# NICBP_v3.net
KiCad netlist of a schematic drawn in EAGLE
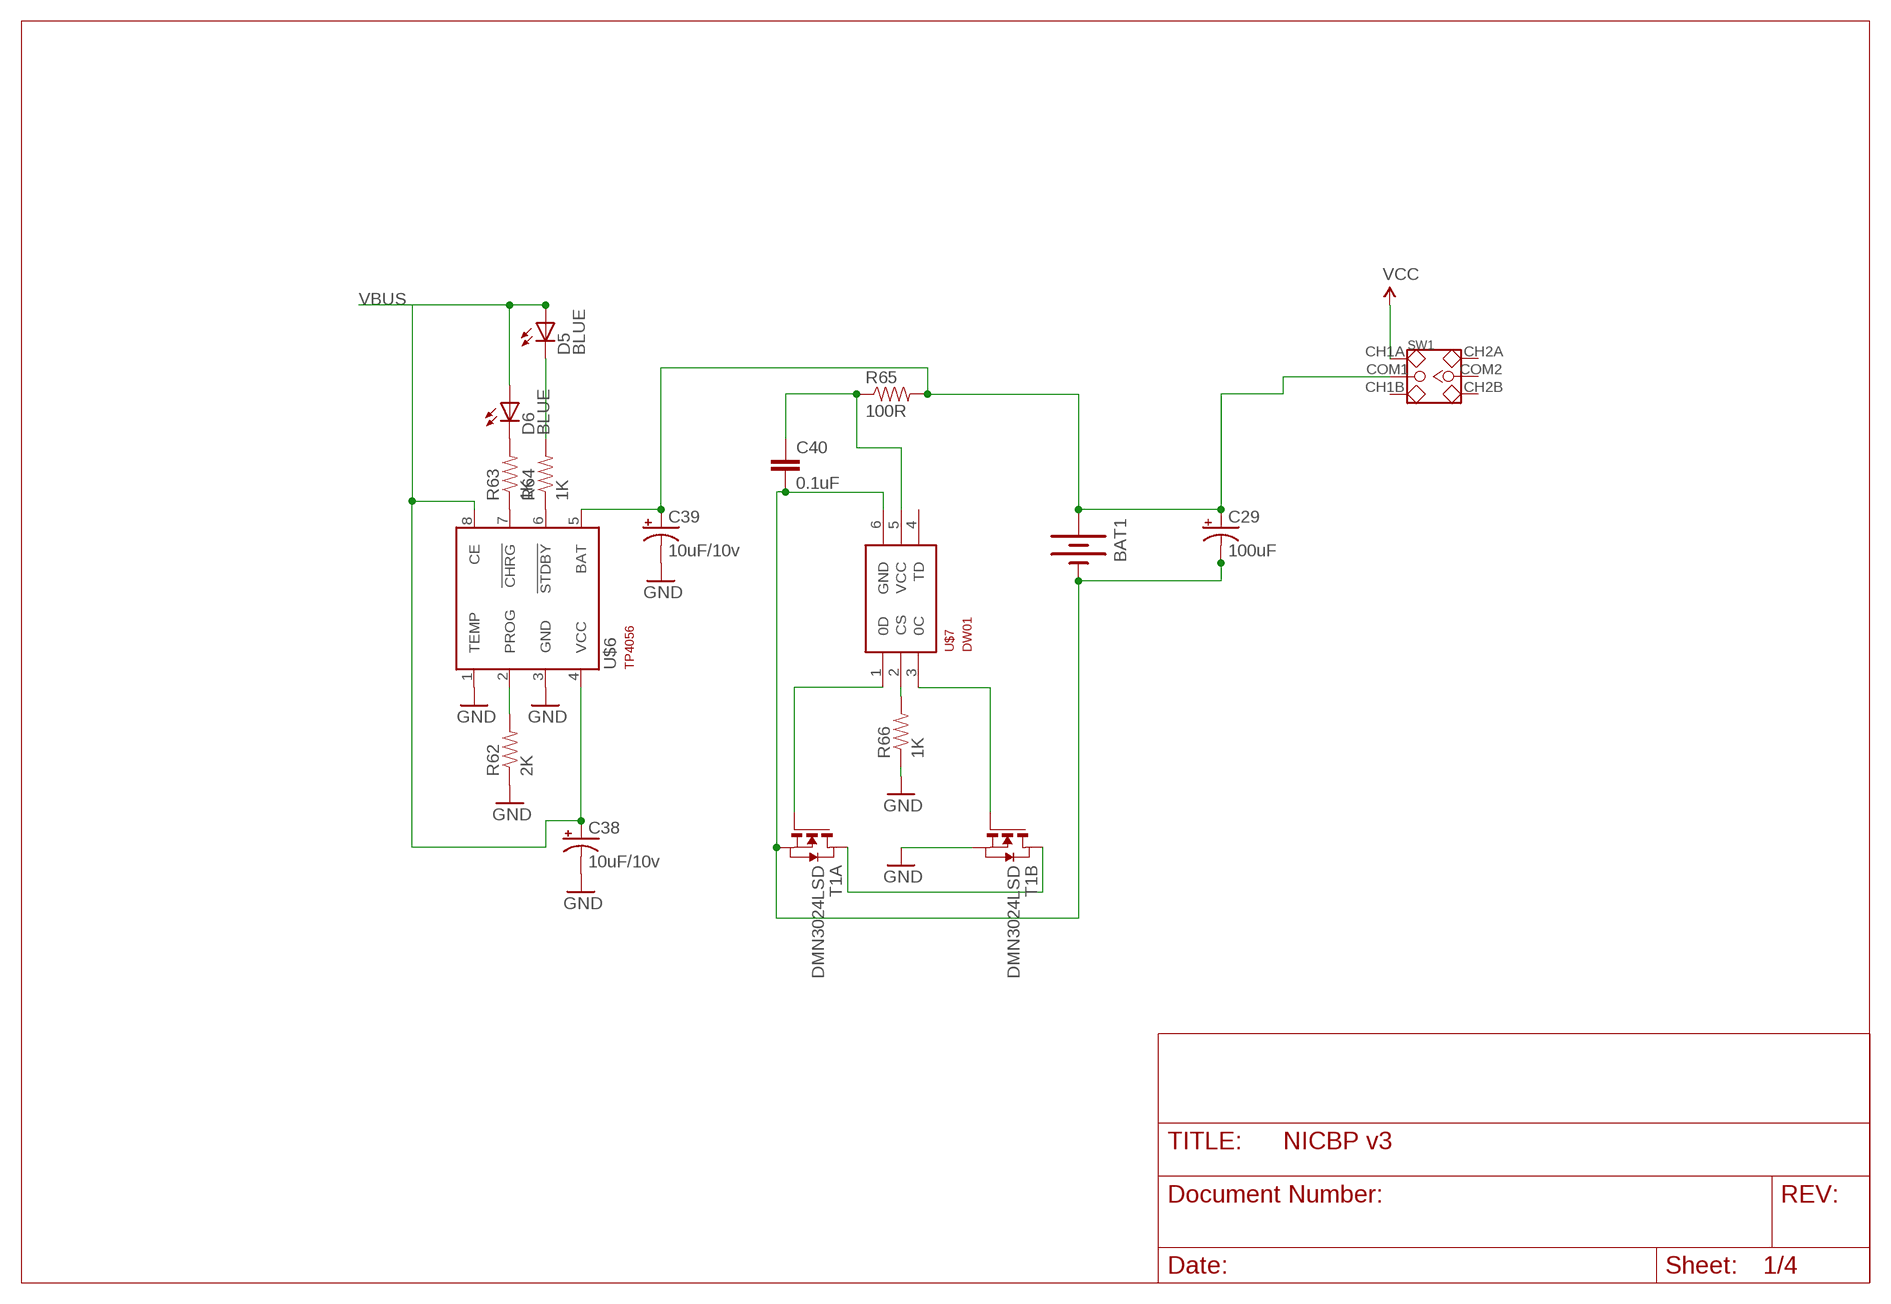
[diagram p0: schematic, sheet 1]
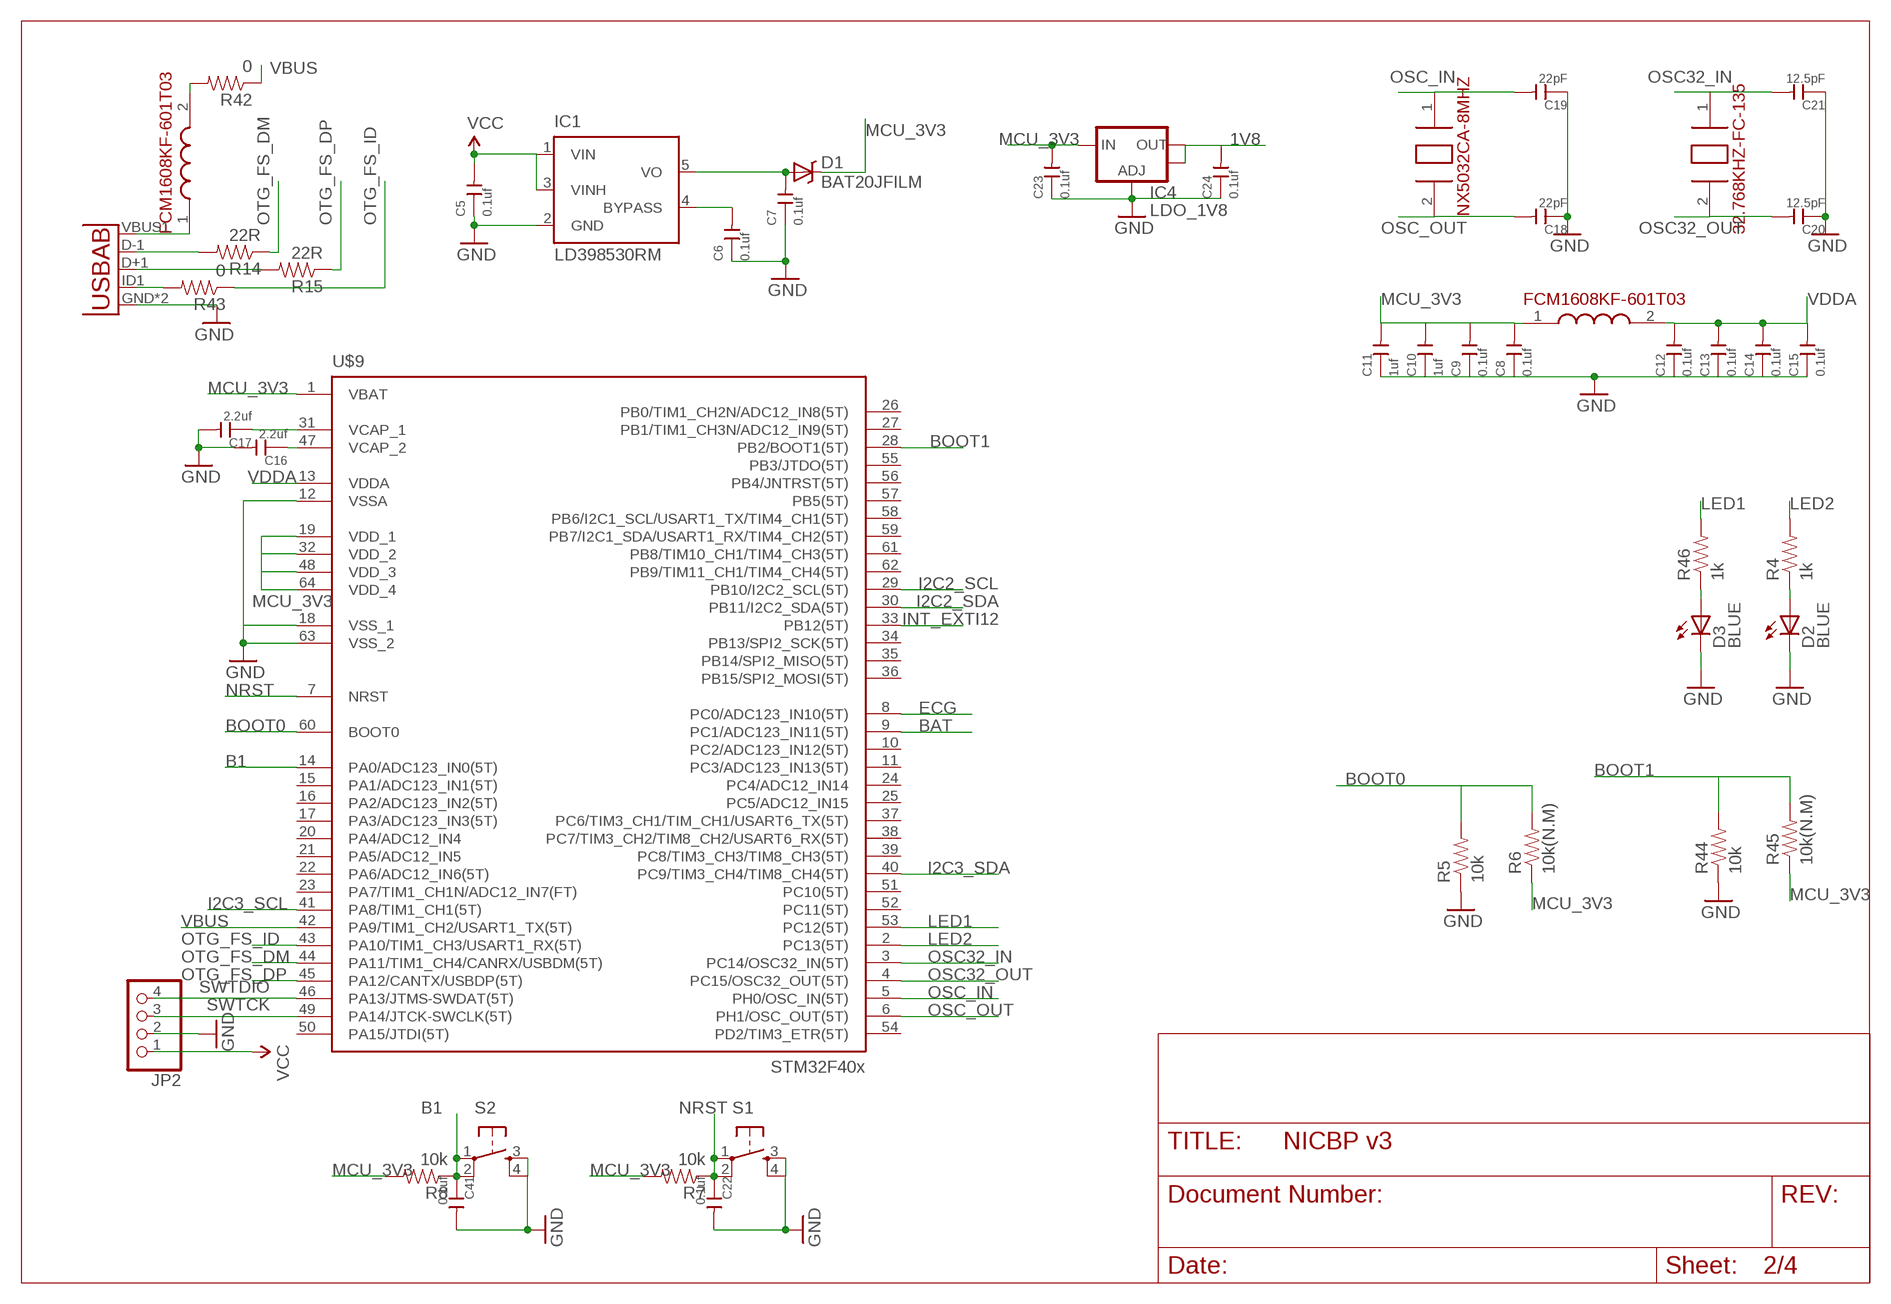
[diagram p1: schematic, sheet 2]
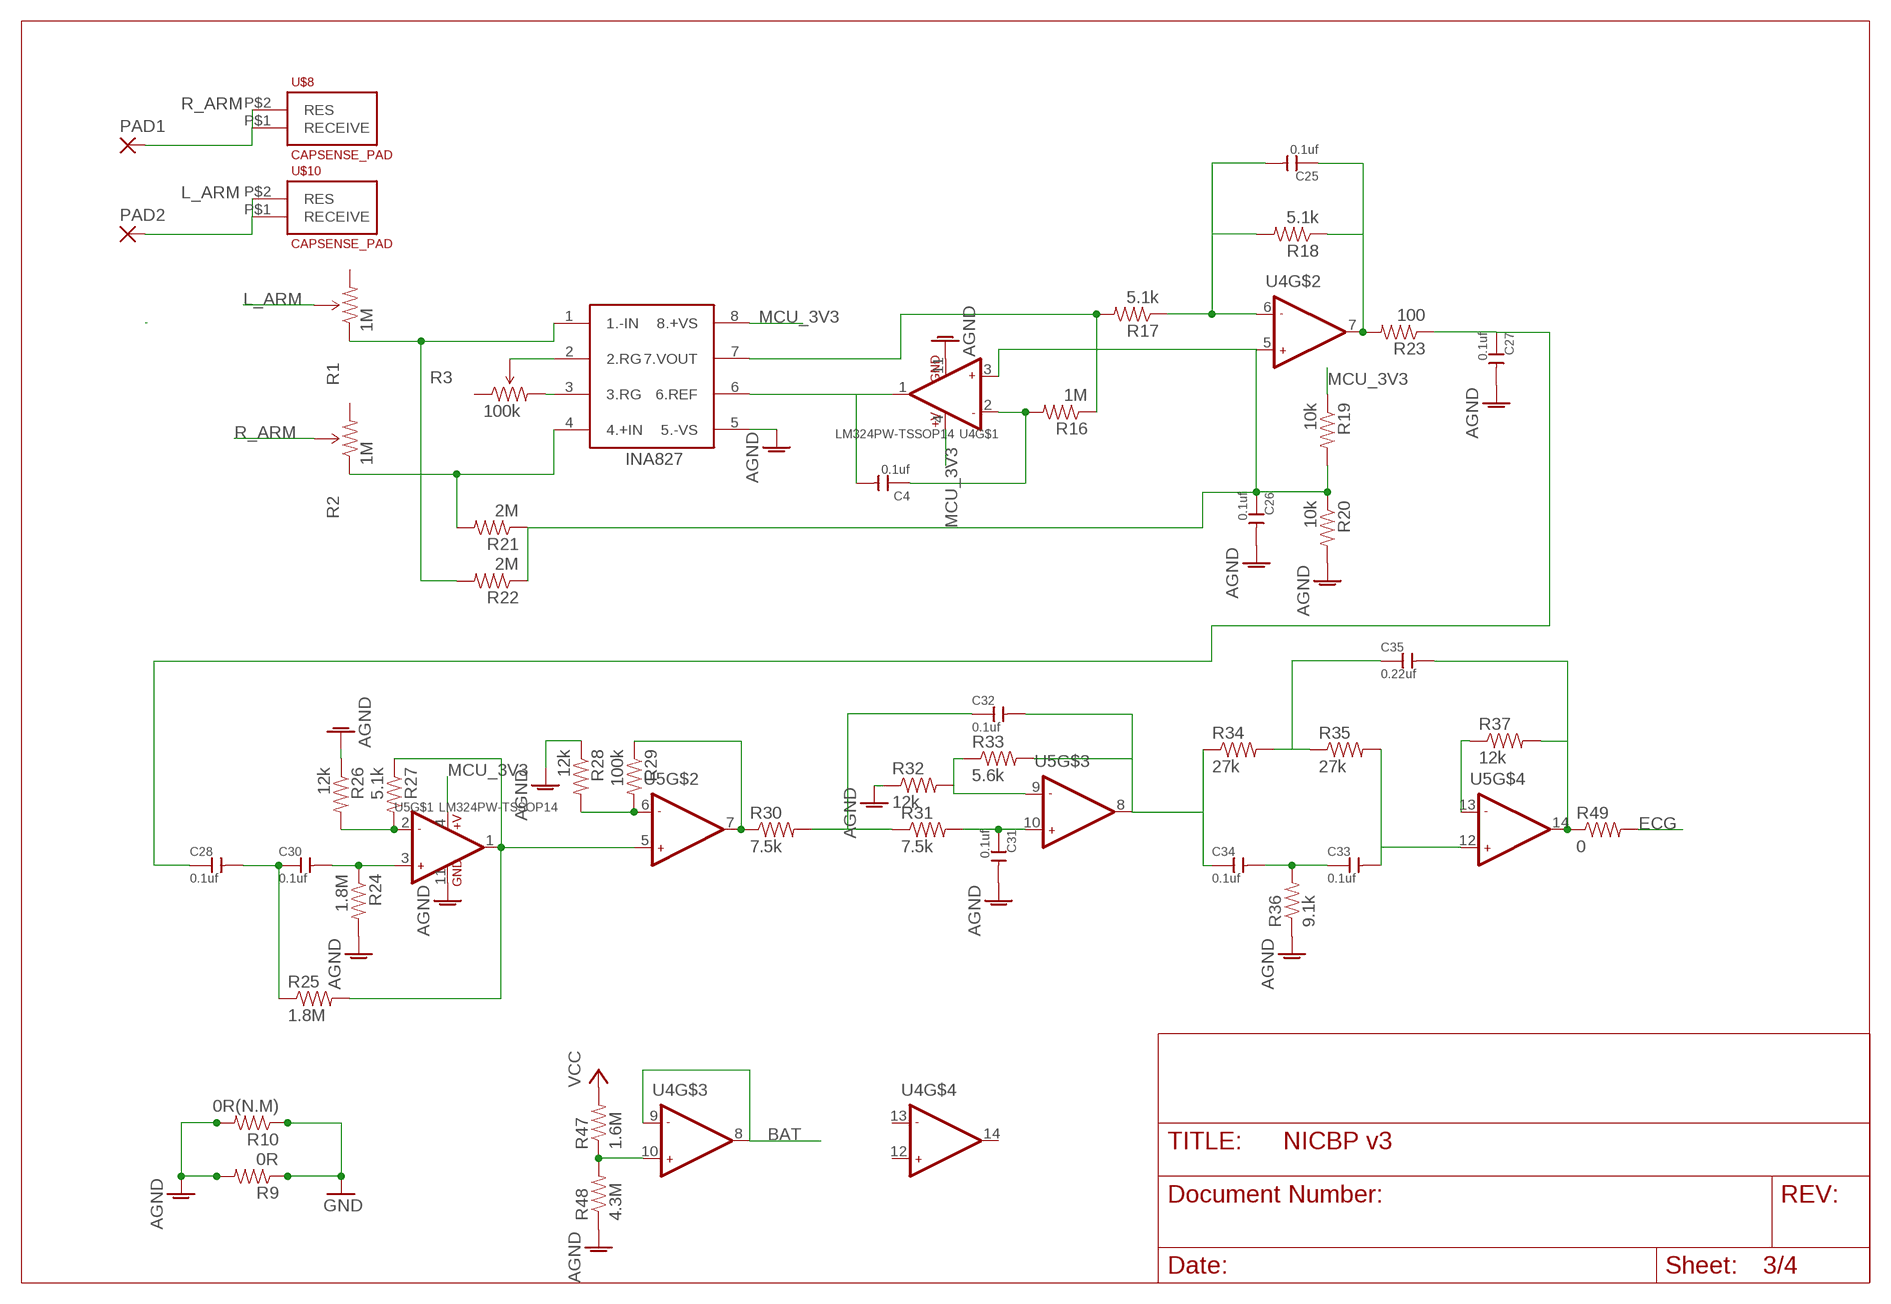
[diagram p2: schematic, sheet 3]
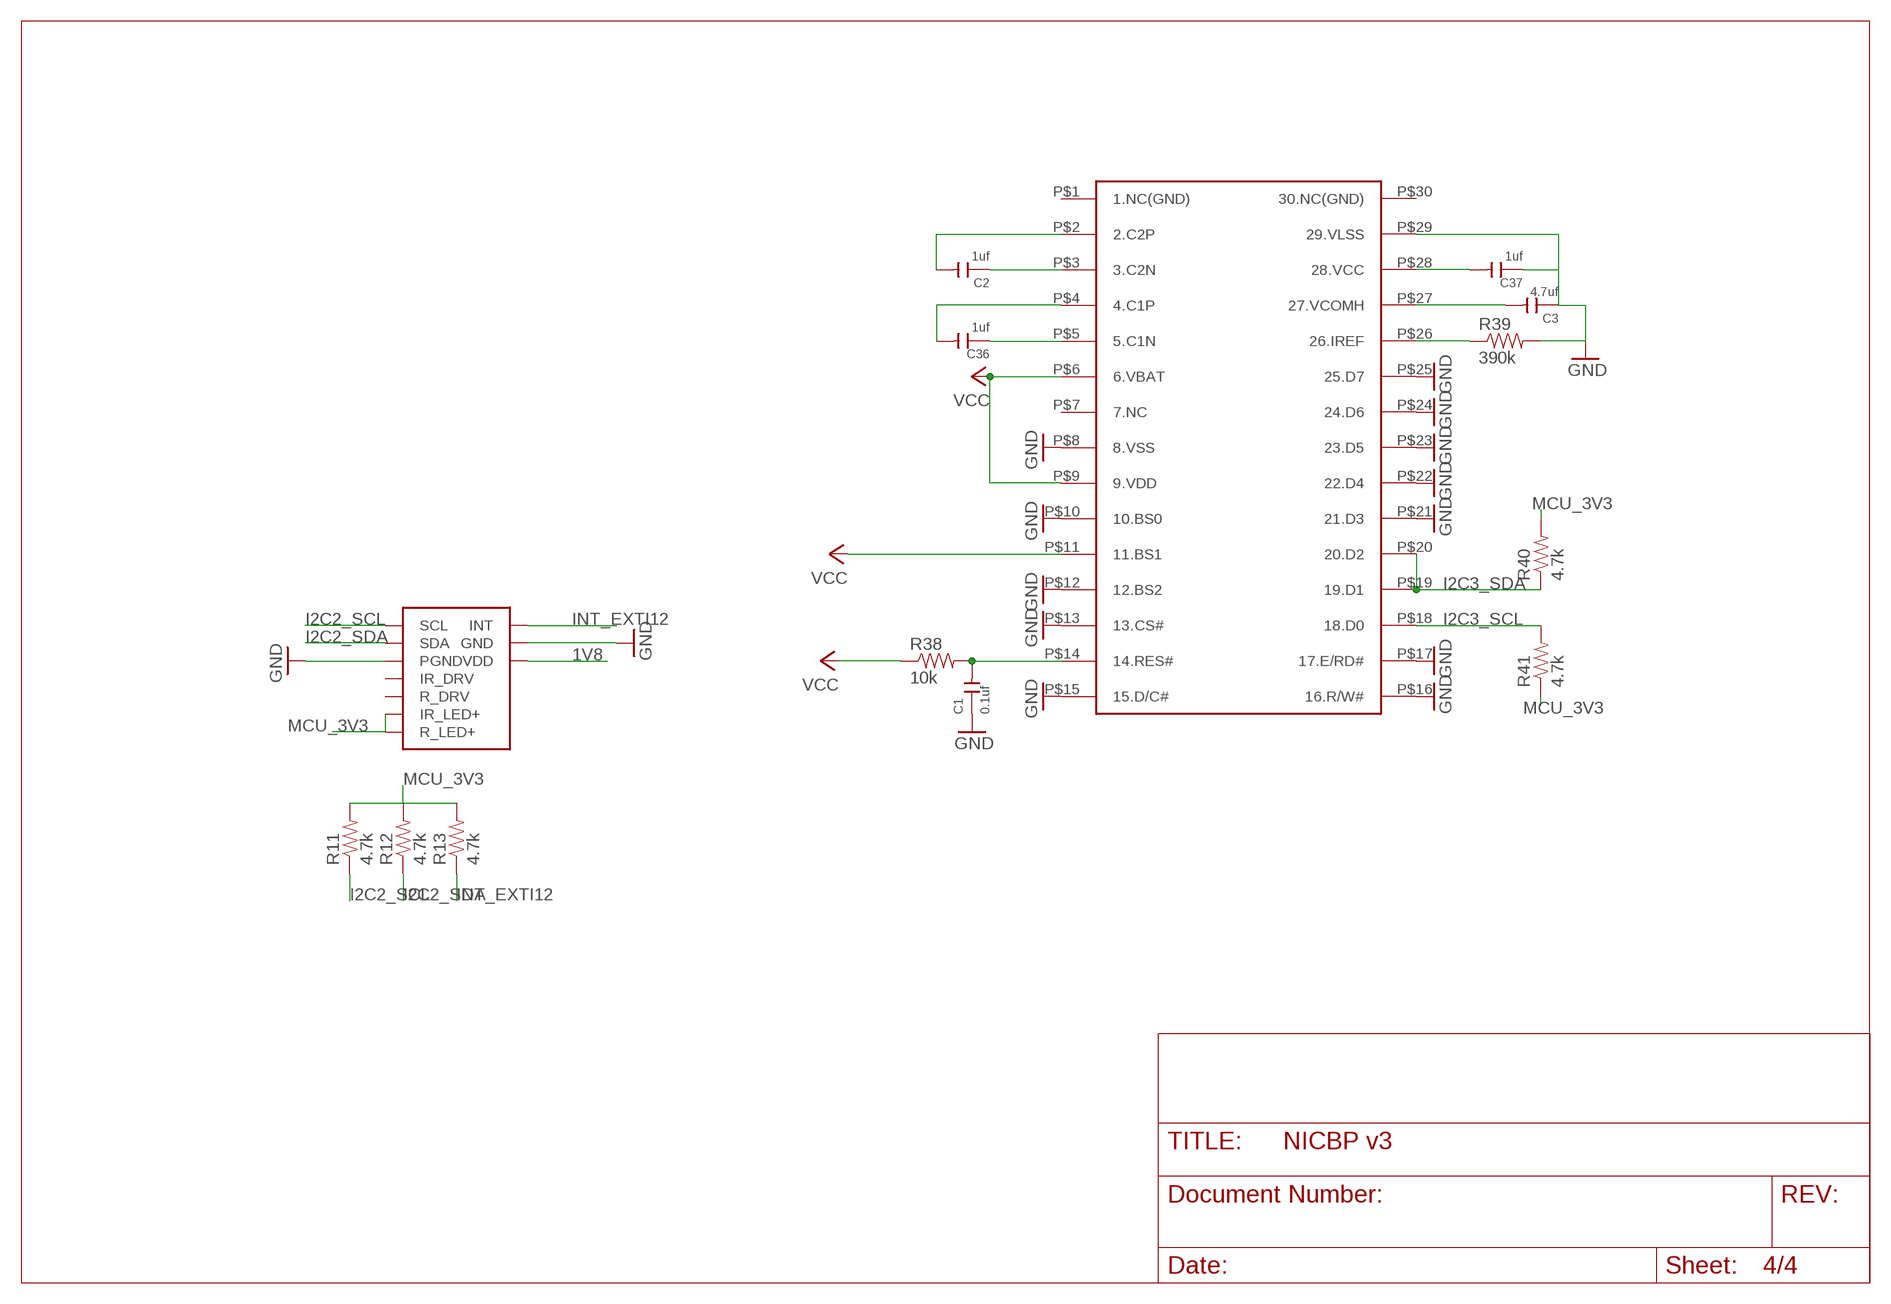
[diagram p3: schematic, sheet 4]

(export (version "E")
  (design (tool "Eeschema 10.0.6"))
  (components
    (comp (ref "BAT1")
      (value "BATTERYLIPO-TABS")
      (footprint "eagle-import:LIPO-110-TABS")
      (libsource (lib "eagle-import") (part "BATTERYLIPO-TABS"))
    )
    (comp (ref "C29")
      (value "100uF")
      (footprint "eagle-import:NIPPON_F80")
      (libsource (lib "eagle-import") (part "CAP_POLF80"))
    )
    (comp (ref "C38")
      (value "10uF/10v")
      (footprint "eagle-import:EIA3216-KIT")
      (libsource (lib "eagle-import") (part "CAP_POL1206-KIT"))
    )
    (comp (ref "C39")
      (value "10uF/10v")
      (footprint "eagle-import:EIA3216-KIT")
      (libsource (lib "eagle-import") (part "CAP_POL1206-KIT"))
    )
    (comp (ref "C40")
      (value "0.1uF")
      (footprint "eagle-import:0603-CAP")
      (libsource (lib "eagle-import") (part "0.1UF-100V-10%(0603)"))
    )
    (comp (ref "D5")
      (value "BLUE")
      (footprint "eagle-import:LED-0603")
      (libsource (lib "eagle-import") (part "LED-BLUE0603"))
    )
    (comp (ref "D6")
      (value "BLUE")
      (footprint "eagle-import:LED-0603")
      (libsource (lib "eagle-import") (part "LED-BLUE0603"))
    )
    (comp (ref "R62")
      (value "2K")
      (footprint "eagle-import:0603-RES")
      (libsource (lib "eagle-import") (part "1KOHM1/10W1%(0603)"))
    )
    (comp (ref "R63")
      (value "1K")
      (footprint "eagle-import:0603-RES")
      (libsource (lib "eagle-import") (part "1KOHM1/10W1%(0603)"))
    )
    (comp (ref "R64")
      (value "1K")
      (footprint "eagle-import:0603-RES")
      (libsource (lib "eagle-import") (part "1KOHM1/10W1%(0603)"))
    )
    (comp (ref "R65")
      (value "100R")
      (footprint "eagle-import:0603-RES")
      (libsource (lib "eagle-import") (part "1KOHM1/10W1%(0603)"))
    )
    (comp (ref "R66")
      (value "1K")
      (footprint "eagle-import:0603-RES")
      (libsource (lib "eagle-import") (part "1KOHM1/10W1%(0603)"))
    )
    (comp (ref "SW1")
      (value "SMD-TOGGLE-SWITCH-2CH(2X3P-7X3.5MM)")
      (footprint "eagle-import:SW6-2.54-SMD-7.0X3.5X1.5MM")
      (libsource (lib "eagle-import") (part "SMD-TOGGLE-SWITCH-2CH(2X3P-7X3.5MM)"))
    )
    (comp (ref "T1")
      (value "DMN3024LSD")
      (footprint "eagle-import:TSSOP-8")
      (libsource (lib "eagle-import") (part "DMN3024LSD"))
    )
    (comp (ref "U$6")
      (value "TP4056")
      (footprint "eagle-import:SOT23-8")
      (libsource (lib "eagle-import") (part "TP4056"))
    )
    (comp (ref "U$7")
      (value "DW01")
      (footprint "eagle-import:SOT23-6")
      (libsource (lib "eagle-import") (part "DW01"))
    )
    (comp (ref "C4")
      (value "0.1uf")
      (footprint "eagle-import:C0603")
      (fields (field (name "MPN") "CC0603KRX5R6BB475"))
      (libsource (lib "eagle-import") (part "CERAMIC-4.7UF-10V-10%-X5R(0603)"))
    )
    (comp (ref "C25")
      (value "0.1uf")
      (footprint "eagle-import:C0603")
      (fields (field (name "MPN") "CC0603KRX5R6BB475"))
      (libsource (lib "eagle-import") (part "CERAMIC-4.7UF-10V-10%-X5R(0603)"))
    )
    (comp (ref "C26")
      (value "0.1uf")
      (footprint "eagle-import:C0603")
      (fields (field (name "MPN") "CC0603KRX5R6BB475"))
      (libsource (lib "eagle-import") (part "CERAMIC-4.7UF-10V-10%-X5R(0603)"))
    )
    (comp (ref "C27")
      (value "0.1uf")
      (footprint "eagle-import:C0603")
      (fields (field (name "MPN") "CC0603KRX5R6BB475"))
      (libsource (lib "eagle-import") (part "CERAMIC-4.7UF-10V-10%-X5R(0603)"))
    )
    (comp (ref "C28")
      (value "0.1uf")
      (footprint "eagle-import:C0603")
      (fields (field (name "MPN") "CC0603KRX5R6BB475"))
      (libsource (lib "eagle-import") (part "CERAMIC-4.7UF-10V-10%-X5R(0603)"))
    )
    (comp (ref "C30")
      (value "0.1uf")
      (footprint "eagle-import:C0603")
      (fields (field (name "MPN") "CC0603KRX5R6BB475"))
      (libsource (lib "eagle-import") (part "CERAMIC-4.7UF-10V-10%-X5R(0603)"))
    )
    (comp (ref "C31")
      (value "0.1uf")
      (footprint "eagle-import:C0603")
      (fields (field (name "MPN") "CC0603KRX5R6BB475"))
      (libsource (lib "eagle-import") (part "CERAMIC-4.7UF-10V-10%-X5R(0603)"))
    )
    (comp (ref "C32")
      (value "0.1uf")
      (footprint "eagle-import:C0603")
      (fields (field (name "MPN") "CC0603KRX5R6BB475"))
      (libsource (lib "eagle-import") (part "CERAMIC-4.7UF-10V-10%-X5R(0603)"))
    )
    (comp (ref "C33")
      (value "0.1uf")
      (footprint "eagle-import:C0603")
      (fields (field (name "MPN") "CC0603KRX5R6BB475"))
      (libsource (lib "eagle-import") (part "CERAMIC-4.7UF-10V-10%-X5R(0603)"))
    )
    (comp (ref "C34")
      (value "0.1uf")
      (footprint "eagle-import:C0603")
      (fields (field (name "MPN") "CC0603KRX5R6BB475"))
      (libsource (lib "eagle-import") (part "CERAMIC-4.7UF-10V-10%-X5R(0603)"))
    )
    (comp (ref "C35")
      (value "0.22uf")
      (footprint "eagle-import:C0603")
      (fields (field (name "MPN") "CC0603KRX5R6BB475"))
      (libsource (lib "eagle-import") (part "CERAMIC-4.7UF-10V-10%-X5R(0603)"))
    )
    (comp (ref "PAD1")
      (value "3,17/1,3")
      (footprint "eagle-import:3,17_1,3")
      (libsource (lib "eagle-import") (part "3,17/1,3"))
    )
    (comp (ref "PAD2")
      (value "3,17/1,3")
      (footprint "eagle-import:3,17_1,3")
      (libsource (lib "eagle-import") (part "3,17/1,3"))
    )
    (comp (ref "R1")
      (value "1M")
      (footprint "eagle-import:TRIMPOT_TC33")
      (libsource (lib "eagle-import") (part "TRIMPOT-2"))
    )
    (comp (ref "R2")
      (value "1M")
      (footprint "eagle-import:TRIMPOT_TC33")
      (libsource (lib "eagle-import") (part "TRIMPOT-2"))
    )
    (comp (ref "R3")
      (value "100k")
      (footprint "eagle-import:TRIMPOT_TC33")
      (libsource (lib "eagle-import") (part "TRIMPOT-2"))
    )
    (comp (ref "R9")
      (value "0R")
      (footprint "eagle-import:0603")
      (libsource (lib "eagle-import") (part "0OHM1/10W5%(0603)"))
    )
    (comp (ref "R10")
      (value "0R(N.M)")
      (footprint "eagle-import:0603")
      (libsource (lib "eagle-import") (part "0OHM1/10W5%(0603)"))
    )
    (comp (ref "R16")
      (value "1M")
      (footprint "eagle-import:0603")
      (libsource (lib "eagle-import") (part "0OHM1/10W5%(0603)"))
    )
    (comp (ref "R17")
      (value "5.1k")
      (footprint "eagle-import:0603")
      (libsource (lib "eagle-import") (part "0OHM1/10W5%(0603)"))
    )
    (comp (ref "R18")
      (value "5.1k")
      (footprint "eagle-import:0603")
      (libsource (lib "eagle-import") (part "0OHM1/10W5%(0603)"))
    )
    (comp (ref "R19")
      (value "10k")
      (footprint "eagle-import:0603")
      (libsource (lib "eagle-import") (part "0OHM1/10W5%(0603)"))
    )
    (comp (ref "R20")
      (value "10k")
      (footprint "eagle-import:0603")
      (libsource (lib "eagle-import") (part "0OHM1/10W5%(0603)"))
    )
    (comp (ref "R21")
      (value "2M")
      (footprint "eagle-import:0603")
      (libsource (lib "eagle-import") (part "0OHM1/10W5%(0603)"))
    )
    (comp (ref "R22")
      (value "2M")
      (footprint "eagle-import:0603")
      (libsource (lib "eagle-import") (part "0OHM1/10W5%(0603)"))
    )
    (comp (ref "R23")
      (value "100")
      (footprint "eagle-import:0603")
      (libsource (lib "eagle-import") (part "0OHM1/10W5%(0603)"))
    )
    (comp (ref "R24")
      (value "1.8M")
      (footprint "eagle-import:0603")
      (libsource (lib "eagle-import") (part "0OHM1/10W5%(0603)"))
    )
    (comp (ref "R25")
      (value "1.8M")
      (footprint "eagle-import:0603")
      (libsource (lib "eagle-import") (part "0OHM1/10W5%(0603)"))
    )
    (comp (ref "R26")
      (value "12k")
      (footprint "eagle-import:0603")
      (libsource (lib "eagle-import") (part "0OHM1/10W5%(0603)"))
    )
    (comp (ref "R27")
      (value "5.1k")
      (footprint "eagle-import:0603")
      (libsource (lib "eagle-import") (part "0OHM1/10W5%(0603)"))
    )
    (comp (ref "R28")
      (value "12k")
      (footprint "eagle-import:0603")
      (libsource (lib "eagle-import") (part "0OHM1/10W5%(0603)"))
    )
    (comp (ref "R29")
      (value "100k")
      (footprint "eagle-import:0603")
      (libsource (lib "eagle-import") (part "0OHM1/10W5%(0603)"))
    )
    (comp (ref "R30")
      (value "7.5k")
      (footprint "eagle-import:0603")
      (libsource (lib "eagle-import") (part "0OHM1/10W5%(0603)"))
    )
    (comp (ref "R31")
      (value "7.5k")
      (footprint "eagle-import:0603")
      (libsource (lib "eagle-import") (part "0OHM1/10W5%(0603)"))
    )
    (comp (ref "R32")
      (value "12k")
      (footprint "eagle-import:0603")
      (libsource (lib "eagle-import") (part "0OHM1/10W5%(0603)"))
    )
    (comp (ref "R33")
      (value "5.6k")
      (footprint "eagle-import:0603")
      (libsource (lib "eagle-import") (part "0OHM1/10W5%(0603)"))
    )
    (comp (ref "R34")
      (value "27k")
      (footprint "eagle-import:0603")
      (libsource (lib "eagle-import") (part "0OHM1/10W5%(0603)"))
    )
    (comp (ref "R35")
      (value "27k")
      (footprint "eagle-import:0603")
      (libsource (lib "eagle-import") (part "0OHM1/10W5%(0603)"))
    )
    (comp (ref "R36")
      (value "9.1k")
      (footprint "eagle-import:0603")
      (libsource (lib "eagle-import") (part "0OHM1/10W5%(0603)"))
    )
    (comp (ref "R37")
      (value "12k")
      (footprint "eagle-import:0603")
      (libsource (lib "eagle-import") (part "0OHM1/10W5%(0603)"))
    )
    (comp (ref "R47")
      (value "1.6M")
      (footprint "eagle-import:0603")
      (libsource (lib "eagle-import") (part "0OHM1/10W5%(0603)"))
    )
    (comp (ref "R48")
      (value "4.3M")
      (footprint "eagle-import:0603")
      (libsource (lib "eagle-import") (part "0OHM1/10W5%(0603)"))
    )
    (comp (ref "R49")
      (value "0")
      (footprint "eagle-import:0603")
      (libsource (lib "eagle-import") (part "0OHM1/10W5%(0603)"))
    )
    (comp (ref "U$5")
      (value "INA827")
      (footprint "eagle-import:INA827")
      (libsource (lib "eagle-import") (part "INA827"))
    )
    (comp (ref "U$8")
      (value "CAPSENSE_PAD")
      (footprint "eagle-import:CAPSENSE_PAD")
      (libsource (lib "eagle-import") (part "CAPSENSE_PAD"))
    )
    (comp (ref "U$10")
      (value "CAPSENSE_PAD")
      (footprint "eagle-import:CAPSENSE_PAD")
      (libsource (lib "eagle-import") (part "CAPSENSE_PAD"))
    )
    (comp (ref "U4")
      (value "LM324PW-TSSOP14")
      (footprint "eagle-import:TSSOP14-0.65-5X4.4MM")
      (fields (field (name "MPN") "LM324PW"))
      (libsource (lib "eagle-import") (part "AMPLIFIER-LM324PW(TSSOP14)"))
    )
    (comp (ref "U5")
      (value "LM324PW-TSSOP14")
      (footprint "eagle-import:TSSOP14-0.65-5X4.4MM")
      (fields (field (name "MPN") "LM324PW"))
      (libsource (lib "eagle-import") (part "AMPLIFIER-LM324PW(TSSOP14)"))
    )
    (comp (ref "C5")
      (value "0.1uf")
      (footprint "eagle-import:C0603")
      (fields (field (name "MPN") "CC0603KRX5R6BB475"))
      (libsource (lib "eagle-import") (part "CERAMIC-4.7UF-10V-10%-X5R(0603)"))
    )
    (comp (ref "C6")
      (value "0.1uf")
      (footprint "eagle-import:C0603")
      (fields (field (name "MPN") "CC0603KRX5R6BB475"))
      (libsource (lib "eagle-import") (part "CERAMIC-4.7UF-10V-10%-X5R(0603)"))
    )
    (comp (ref "C7")
      (value "0.1uf")
      (footprint "eagle-import:C0603")
      (fields (field (name "MPN") "CC0603KRX5R6BB475"))
      (libsource (lib "eagle-import") (part "CERAMIC-4.7UF-10V-10%-X5R(0603)"))
    )
    (comp (ref "C8")
      (value "0.1uf")
      (footprint "eagle-import:C0603")
      (fields (field (name "MPN") "CC0603KRX5R6BB475"))
      (libsource (lib "eagle-import") (part "CERAMIC-4.7UF-10V-10%-X5R(0603)"))
    )
    (comp (ref "C9")
      (value "0.1uf")
      (footprint "eagle-import:C0603")
      (fields (field (name "MPN") "CC0603KRX5R6BB475"))
      (libsource (lib "eagle-import") (part "CERAMIC-4.7UF-10V-10%-X5R(0603)"))
    )
    (comp (ref "C10")
      (value "1uf")
      (footprint "eagle-import:C0603")
      (fields (field (name "MPN") "CC0603KRX5R6BB475"))
      (libsource (lib "eagle-import") (part "CERAMIC-4.7UF-10V-10%-X5R(0603)"))
    )
    (comp (ref "C11")
      (value "1uf")
      (footprint "eagle-import:C0603")
      (fields (field (name "MPN") "CC0603KRX5R6BB475"))
      (libsource (lib "eagle-import") (part "CERAMIC-4.7UF-10V-10%-X5R(0603)"))
    )
    (comp (ref "C12")
      (value "0.1uf")
      (footprint "eagle-import:C0603")
      (fields (field (name "MPN") "CC0603KRX5R6BB475"))
      (libsource (lib "eagle-import") (part "CERAMIC-4.7UF-10V-10%-X5R(0603)"))
    )
    (comp (ref "C13")
      (value "0.1uf")
      (footprint "eagle-import:C0603")
      (fields (field (name "MPN") "CC0603KRX5R6BB475"))
      (libsource (lib "eagle-import") (part "CERAMIC-4.7UF-10V-10%-X5R(0603)"))
    )
    (comp (ref "C14")
      (value "0.1uf")
      (footprint "eagle-import:C0603")
      (fields (field (name "MPN") "CC0603KRX5R6BB475"))
      (libsource (lib "eagle-import") (part "CERAMIC-4.7UF-10V-10%-X5R(0603)"))
    )
    (comp (ref "C15")
      (value "0.1uf")
      (footprint "eagle-import:C0603")
      (fields (field (name "MPN") "CC0603KRX5R6BB475"))
      (libsource (lib "eagle-import") (part "CERAMIC-4.7UF-10V-10%-X5R(0603)"))
    )
    (comp (ref "C16")
      (value "2.2uf")
      (footprint "eagle-import:C0603")
      (fields (field (name "MPN") "CC0603KRX5R6BB475"))
      (libsource (lib "eagle-import") (part "CERAMIC-4.7UF-10V-10%-X5R(0603)"))
    )
    (comp (ref "C17")
      (value "2.2uf")
      (footprint "eagle-import:C0603")
      (fields (field (name "MPN") "CC0603KRX5R6BB475"))
      (libsource (lib "eagle-import") (part "CERAMIC-4.7UF-10V-10%-X5R(0603)"))
    )
    (comp (ref "C18")
      (value "22pF")
      (footprint "eagle-import:C0603")
      (fields (field (name "MPN") "CC0603KRX5R6BB475"))
      (libsource (lib "eagle-import") (part "CERAMIC-4.7UF-10V-10%-X5R(0603)"))
    )
    (comp (ref "C19")
      (value "22pF")
      (footprint "eagle-import:C0603")
      (fields (field (name "MPN") "CC0603KRX5R6BB475"))
      (libsource (lib "eagle-import") (part "CERAMIC-4.7UF-10V-10%-X5R(0603)"))
    )
    (comp (ref "C20")
      (value "12.5pF")
      (footprint "eagle-import:C0603")
      (fields (field (name "MPN") "CC0603KRX5R6BB475"))
      (libsource (lib "eagle-import") (part "CERAMIC-4.7UF-10V-10%-X5R(0603)"))
    )
    (comp (ref "C21")
      (value "12.5pF")
      (footprint "eagle-import:C0603")
      (fields (field (name "MPN") "CC0603KRX5R6BB475"))
      (libsource (lib "eagle-import") (part "CERAMIC-4.7UF-10V-10%-X5R(0603)"))
    )
    (comp (ref "C22")
      (value "0.1uf")
      (footprint "eagle-import:C0603")
      (fields (field (name "MPN") "CC0603KRX5R6BB475"))
      (libsource (lib "eagle-import") (part "CERAMIC-4.7UF-10V-10%-X5R(0603)"))
    )
    (comp (ref "C23")
      (value "0.1uf")
      (footprint "eagle-import:C0603")
      (fields (field (name "MPN") "CC0603KRX5R6BB475"))
      (libsource (lib "eagle-import") (part "CERAMIC-4.7UF-10V-10%-X5R(0603)"))
    )
    (comp (ref "C24")
      (value "0.1uf")
      (footprint "eagle-import:C0603")
      (fields (field (name "MPN") "CC0603KRX5R6BB475"))
      (libsource (lib "eagle-import") (part "CERAMIC-4.7UF-10V-10%-X5R(0603)"))
    )
    (comp (ref "C41")
      (value "0.1uf")
      (footprint "eagle-import:C0603")
      (fields (field (name "MPN") "CC0603KRX5R6BB475"))
      (libsource (lib "eagle-import") (part "CERAMIC-4.7UF-10V-10%-X5R(0603)"))
    )
    (comp (ref "D1")
      (value "BAT20JFILM")
      (footprint "eagle-import:SOD-323")
      (libsource (lib "eagle-import") (part "BAT20JFILM"))
    )
    (comp (ref "D2")
      (value "BLUE")
      (footprint "eagle-import:LED-0603")
      (libsource (lib "eagle-import") (part "LED-BLUE0603"))
    )
    (comp (ref "D3")
      (value "BLUE")
      (footprint "eagle-import:LED-0603")
      (libsource (lib "eagle-import") (part "LED-BLUE0603"))
    )
    (comp (ref "IC1")
      (value "LD398530RM")
      (footprint "eagle-import:SOT23-5L")
      (libsource (lib "eagle-import") (part "LD3985M30R"))
    )
    (comp (ref "IC4")
      (value "LDO_1V8")
      (footprint "eagle-import:SOT223")
      (libsource (lib "eagle-import") (part "V_REG_LM1117SOT223"))
    )
    (comp (ref "JP2")
      (value "PINHD-1X4")
      (footprint "eagle-import:1X04")
      (libsource (lib "eagle-import") (part "PINHD-1X4"))
    )
    (comp (ref "R4")
      (value "1k")
      (footprint "eagle-import:0603")
      (libsource (lib "eagle-import") (part "0OHM1/10W5%(0603)"))
    )
    (comp (ref "R5")
      (value "10k")
      (footprint "eagle-import:0603")
      (libsource (lib "eagle-import") (part "0OHM1/10W5%(0603)"))
    )
    (comp (ref "R6")
      (value "10k(N.M)")
      (footprint "eagle-import:0603")
      (libsource (lib "eagle-import") (part "0OHM1/10W5%(0603)"))
    )
    (comp (ref "R7")
      (value "10k")
      (footprint "eagle-import:0603")
      (libsource (lib "eagle-import") (part "0OHM1/10W5%(0603)"))
    )
    (comp (ref "R8")
      (value "10k")
      (footprint "eagle-import:0603")
      (libsource (lib "eagle-import") (part "0OHM1/10W5%(0603)"))
    )
    (comp (ref "R14")
      (value "22R")
      (footprint "eagle-import:0603-RES")
      (libsource (lib "eagle-import") (part "390OHM1/10W1%(0603)"))
    )
    (comp (ref "R15")
      (value "22R")
      (footprint "eagle-import:0603-RES")
      (libsource (lib "eagle-import") (part "390OHM1/10W1%(0603)"))
    )
    (comp (ref "R42")
      (value "0")
      (footprint "eagle-import:0603-RES")
      (libsource (lib "eagle-import") (part "390OHM1/10W1%(0603)"))
    )
    (comp (ref "R43")
      (value "0")
      (footprint "eagle-import:0603-RES")
      (libsource (lib "eagle-import") (part "390OHM1/10W1%(0603)"))
    )
    (comp (ref "R44")
      (value "10k")
      (footprint "eagle-import:0603")
      (libsource (lib "eagle-import") (part "0OHM1/10W5%(0603)"))
    )
    (comp (ref "R45")
      (value "10k(N.M)")
      (footprint "eagle-import:0603")
      (libsource (lib "eagle-import") (part "0OHM1/10W5%(0603)"))
    )
    (comp (ref "R46")
      (value "1k")
      (footprint "eagle-import:0603")
      (libsource (lib "eagle-import") (part "0OHM1/10W5%(0603)"))
    )
    (comp (ref "S1")
      (value "TAC_SWITCHSMD")
      (footprint "eagle-import:TACTILE_SWITCH_SMD")
      (libsource (lib "eagle-import") (part "TAC_SWITCHSMD"))
    )
    (comp (ref "S2")
      (value "TAC_SWITCHSMD")
      (footprint "eagle-import:TACTILE_SWITCH_SMD")
      (libsource (lib "eagle-import") (part "TAC_SWITCHSMD"))
    )
    (comp (ref "U$2")
      (value "NX5032CA-8MHZ")
      (footprint "eagle-import:NX5032CA-8MHZ")
      (libsource (lib "eagle-import") (part "NX5032CA-8MHZ"))
    )
    (comp (ref "U$3")
      (value "FCM1608KF-601T03")
      (footprint "eagle-import:FCM1608KF-601T03")
      (libsource (lib "eagle-import") (part "FCM1608KF-601T03"))
    )
    (comp (ref "U$4")
      (value "32.768KHZ-FC-135")
      (footprint "eagle-import:32.768KHZ-FC-135")
      (libsource (lib "eagle-import") (part "32.768KHZ-FC-135"))
    )
    (comp (ref "U$9")
      (value "STM32F405R")
      (footprint "eagle-import:TQFP64")
      (libsource (lib "eagle-import") (part "STM32F405R"))
    )
    (comp (ref "U$15")
      (value "FCM1608KF-601T03")
      (footprint "eagle-import:FCM1608KF-601T03")
      (libsource (lib "eagle-import") (part "FCM1608KF-601T03"))
    )
    (comp (ref "U1")
      (value "USB\"\"")
      (footprint "eagle-import:USB-MICRO-SMD")
      (libsource (lib "eagle-import") (part "USB{dblquote}{dblquote}"))
    )
    (comp (ref "C1")
      (value "0.1uf")
      (footprint "eagle-import:C0603")
      (fields (field (name "MPN") "CC0603KRX5R6BB475"))
      (libsource (lib "eagle-import") (part "CERAMIC-4.7UF-10V-10%-X5R(0603)"))
    )
    (comp (ref "C2")
      (value "1uf")
      (footprint "eagle-import:C0603")
      (fields (field (name "MPN") "CC0603KRX5R6BB475"))
      (libsource (lib "eagle-import") (part "CERAMIC-4.7UF-10V-10%-X5R(0603)"))
    )
    (comp (ref "C3")
      (value "4.7uf")
      (footprint "eagle-import:C0603")
      (fields (field (name "MPN") "CC0603KRX5R6BB475"))
      (libsource (lib "eagle-import") (part "CERAMIC-4.7UF-10V-10%-X5R(0603)"))
    )
    (comp (ref "C36")
      (value "1uf")
      (footprint "eagle-import:C0603")
      (fields (field (name "MPN") "CC0603KRX5R6BB475"))
      (libsource (lib "eagle-import") (part "CERAMIC-4.7UF-10V-10%-X5R(0603)"))
    )
    (comp (ref "C37")
      (value "1uf")
      (footprint "eagle-import:C0603")
      (fields (field (name "MPN") "CC0603KRX5R6BB475"))
      (libsource (lib "eagle-import") (part "CERAMIC-4.7UF-10V-10%-X5R(0603)"))
    )
    (comp (ref "R11")
      (value "4.7k")
      (footprint "eagle-import:0603")
      (libsource (lib "eagle-import") (part "0OHM1/10W5%(0603)"))
    )
    (comp (ref "R12")
      (value "4.7k")
      (footprint "eagle-import:0603")
      (libsource (lib "eagle-import") (part "0OHM1/10W5%(0603)"))
    )
    (comp (ref "R13")
      (value "4.7k")
      (footprint "eagle-import:0603")
      (libsource (lib "eagle-import") (part "0OHM1/10W5%(0603)"))
    )
    (comp (ref "R38")
      (value "10k")
      (footprint "eagle-import:0603")
      (libsource (lib "eagle-import") (part "0OHM1/10W5%(0603)"))
    )
    (comp (ref "R39")
      (value "390k")
      (footprint "eagle-import:0603")
      (libsource (lib "eagle-import") (part "0OHM1/10W5%(0603)"))
    )
    (comp (ref "R40")
      (value "4.7k")
      (footprint "eagle-import:0603")
      (libsource (lib "eagle-import") (part "0OHM1/10W5%(0603)"))
    )
    (comp (ref "R41")
      (value "4.7k")
      (footprint "eagle-import:0603")
      (libsource (lib "eagle-import") (part "0OHM1/10W5%(0603)"))
    )
    (comp (ref "U$12")
      (value "MAX30100")
      (footprint "eagle-import:MAX30100")
      (libsource (lib "eagle-import") (part "MAX30100"))
    )
    (comp (ref "U$13")
      (value "ER-OLED0.96")
      (footprint "eagle-import:ER-OLED0.96")
      (libsource (lib "eagle-import") (part "ER-OLED0.96"))
    )
  )
  (nets
    (net (code "1") (name "1V8") (class "Default")
      (node (ref "C24") (pin "2") (pinfunction "2_2") (pintype "passive"))
      (node (ref "IC4") (pin "2") (pinfunction "OUT_2") (pintype "output"))
      (node (ref "IC4") (pin "4") (pinfunction "OUT_4") (pintype "output"))
      (node (ref "U$12") (pin "11") (pinfunction "VDD_11") (pintype "bidirectional"))
    )
    (net (code "2") (name "AGND") (class "Default")
      (node (ref "C26") (pin "2") (pinfunction "2_2") (pintype "passive"))
      (node (ref "C27") (pin "2") (pinfunction "2_2") (pintype "passive"))
      (node (ref "C31") (pin "2") (pinfunction "2_2") (pintype "passive"))
      (node (ref "R10") (pin "2") (pinfunction "2_2") (pintype "passive"))
      (node (ref "R20") (pin "2") (pinfunction "2_2") (pintype "passive"))
      (node (ref "R24") (pin "2") (pinfunction "2_2") (pintype "passive"))
      (node (ref "R26") (pin "1") (pinfunction "1_1") (pintype "passive"))
      (node (ref "R28") (pin "1") (pinfunction "1_1") (pintype "passive"))
      (node (ref "R32") (pin "1") (pinfunction "1_1") (pintype "passive"))
      (node (ref "R36") (pin "1") (pinfunction "1_1") (pintype "passive"))
      (node (ref "R48") (pin "1") (pinfunction "1_1") (pintype "passive"))
      (node (ref "R9") (pin "2") (pinfunction "2_2") (pintype "passive"))
      (node (ref "U$5") (pin "5") (pinfunction "5.-VS_5") (pintype "bidirectional"))
      (node (ref "U4") (pin "11") (pinfunction "GND_11") (pintype "power_in"))
      (node (ref "U5") (pin "11") (pinfunction "GND_11") (pintype "power_in"))
    )
    (net (code "3") (name "B1") (class "Default")
      (node (ref "C41") (pin "1") (pinfunction "1_1") (pintype "passive"))
      (node (ref "R8") (pin "1") (pinfunction "1_1") (pintype "passive"))
      (node (ref "S2") (pin "1") (pinfunction "1_1") (pintype "passive"))
      (node (ref "S2") (pin "2") (pinfunction "2_2") (pintype "passive"))
      (node (ref "U$9") (pin "14") (pinfunction "PA0/ADC123_IN0(5T)_14") (pintype "bidirectional"))
    )
    (net (code "4") (name "BAT") (class "Default")
      (node (ref "U$9") (pin "9") (pinfunction "PC1/ADC123_IN11(5T)_9") (pintype "bidirectional"))
      (node (ref "U4") (pin "8") (pinfunction "OUT2_8") (pintype "output"))
      (node (ref "U4") (pin "9") (pinfunction "-IN2_9") (pintype "input"))
    )
    (net (code "5") (name "BOOT0") (class "Default")
      (node (ref "R5") (pin "2") (pinfunction "2_2") (pintype "passive"))
      (node (ref "R6") (pin "2") (pinfunction "2_2") (pintype "passive"))
      (node (ref "U$9") (pin "60") (pinfunction "BOOT0_60") (pintype "bidirectional"))
    )
    (net (code "6") (name "BOOT1") (class "Default")
      (node (ref "R44") (pin "2") (pinfunction "2_2") (pintype "passive"))
      (node (ref "R45") (pin "2") (pinfunction "2_2") (pintype "passive"))
      (node (ref "U$9") (pin "28") (pinfunction "PB2/BOOT1(5T)_28") (pintype "bidirectional"))
    )
    (net (code "7") (name "ECG") (class "Default")
      (node (ref "R49") (pin "2") (pinfunction "2_2") (pintype "passive"))
      (node (ref "U$9") (pin "8") (pinfunction "PC0/ADC123_IN10(5T)_8") (pintype "bidirectional"))
    )
    (net (code "8") (name "GND") (class "Default")
      (node (ref "C1") (pin "1") (pinfunction "1_1") (pintype "passive"))
      (node (ref "C10") (pin "1") (pinfunction "1_1") (pintype "passive"))
      (node (ref "C11") (pin "1") (pinfunction "1_1") (pintype "passive"))
      (node (ref "C12") (pin "1") (pinfunction "1_1") (pintype "passive"))
      (node (ref "C13") (pin "1") (pinfunction "1_1") (pintype "passive"))
      (node (ref "C14") (pin "1") (pinfunction "1_1") (pintype "passive"))
      (node (ref "C15") (pin "1") (pinfunction "1_1") (pintype "passive"))
      (node (ref "C16") (pin "2") (pinfunction "2_2") (pintype "passive"))
      (node (ref "C17") (pin "2") (pinfunction "2_2") (pintype "passive"))
      (node (ref "C18") (pin "1") (pinfunction "1_1") (pintype "passive"))
      (node (ref "C19") (pin "1") (pinfunction "1_1") (pintype "passive"))
      (node (ref "C20") (pin "1") (pinfunction "1_1") (pintype "passive"))
      (node (ref "C21") (pin "1") (pinfunction "1_1") (pintype "passive"))
      (node (ref "C22") (pin "2") (pinfunction "2_2") (pintype "passive"))
      (node (ref "C23") (pin "1") (pinfunction "1_1") (pintype "passive"))
      (node (ref "C24") (pin "1") (pinfunction "1_1") (pintype "passive"))
      (node (ref "C3") (pin "1") (pinfunction "1_1") (pintype "passive"))
      (node (ref "C37") (pin "1") (pinfunction "1_1") (pintype "passive"))
      (node (ref "C38") (pin "C") (pinfunction "-_C") (pintype "passive"))
      (node (ref "C39") (pin "C") (pinfunction "-_C") (pintype "passive"))
      (node (ref "C41") (pin "2") (pinfunction "2_2") (pintype "passive"))
      (node (ref "C5") (pin "1") (pinfunction "1_1") (pintype "passive"))
      (node (ref "C6") (pin "1") (pinfunction "1_1") (pintype "passive"))
      (node (ref "C7") (pin "1") (pinfunction "1_1") (pintype "passive"))
      (node (ref "C8") (pin "1") (pinfunction "1_1") (pintype "passive"))
      (node (ref "C9") (pin "1") (pinfunction "1_1") (pintype "passive"))
      (node (ref "D2") (pin "C") (pinfunction "C_C") (pintype "passive"))
      (node (ref "D3") (pin "C") (pinfunction "C_C") (pintype "passive"))
      (node (ref "IC1") (pin "2") (pinfunction "GND_2") (pintype "power_in"))
      (node (ref "IC4") (pin "1") (pinfunction "ADJ_1") (pintype "input"))
      (node (ref "JP2") (pin "2") (pinfunction "2_2") (pintype "passive"))
      (node (ref "R10") (pin "1") (pinfunction "1_1") (pintype "passive"))
      (node (ref "R39") (pin "2") (pinfunction "2_2") (pintype "passive"))
      (node (ref "R44") (pin "1") (pinfunction "1_1") (pintype "passive"))
      (node (ref "R5") (pin "1") (pinfunction "1_1") (pintype "passive"))
      (node (ref "R62") (pin "1") (pinfunction "1_1") (pintype "passive"))
      (node (ref "R66") (pin "1") (pinfunction "1_1") (pintype "passive"))
      (node (ref "R9") (pin "1") (pinfunction "1_1") (pintype "passive"))
      (node (ref "S1") (pin "3") (pinfunction "3_3") (pintype "passive"))
      (node (ref "S1") (pin "4") (pinfunction "4_4") (pintype "passive"))
      (node (ref "S2") (pin "3") (pinfunction "3_3") (pintype "passive"))
      (node (ref "S2") (pin "4") (pinfunction "4_4") (pintype "passive"))
      (node (ref "T1") (pin "6") (pinfunction "S_6") (pintype "passive"))
      (node (ref "T1") (pin "7") (pinfunction "S_7") (pintype "passive"))
      (node (ref "U$12") (pin "12") (pinfunction "GND_12") (pintype "bidirectional"))
      (node (ref "U$12") (pin "4") (pinfunction "PGND_4") (pintype "bidirectional"))
      (node (ref "U$13") (pin "P$10") (pinfunction "10.BS0_P$10") (pintype "bidirectional"))
      (node (ref "U$13") (pin "P$12") (pinfunction "12.BS2_P$12") (pintype "bidirectional"))
      (node (ref "U$13") (pin "P$13") (pinfunction "13.CS#_P$13") (pintype "bidirectional"))
      (node (ref "U$13") (pin "P$15") (pinfunction "15.D/C#_P$15") (pintype "bidirectional"))
      (node (ref "U$13") (pin "P$16") (pinfunction "16.R/W#_P$16") (pintype "bidirectional"))
      (node (ref "U$13") (pin "P$17") (pinfunction "17.E/RD#_P$17") (pintype "bidirectional"))
      (node (ref "U$13") (pin "P$21") (pinfunction "21.D3_P$21") (pintype "bidirectional"))
      (node (ref "U$13") (pin "P$22") (pinfunction "22.D4_P$22") (pintype "bidirectional"))
      (node (ref "U$13") (pin "P$23") (pinfunction "23.D5_P$23") (pintype "bidirectional"))
      (node (ref "U$13") (pin "P$24") (pinfunction "24.D6_P$24") (pintype "bidirectional"))
      (node (ref "U$13") (pin "P$25") (pinfunction "25.D7_P$25") (pintype "bidirectional"))
      (node (ref "U$13") (pin "P$29") (pinfunction "29.VLSS_P$29") (pintype "bidirectional"))
      (node (ref "U$13") (pin "P$8") (pinfunction "8.VSS_P$8") (pintype "bidirectional"))
      (node (ref "U$6") (pin "1") (pinfunction "TEMP_1") (pintype "bidirectional"))
      (node (ref "U$6") (pin "3") (pinfunction "GND_3") (pintype "bidirectional"))
      (node (ref "U$9") (pin "12") (pinfunction "VSSA_12") (pintype "bidirectional"))
      (node (ref "U$9") (pin "18") (pinfunction "VSS_1_18") (pintype "bidirectional"))
      (node (ref "U$9") (pin "63") (pinfunction "VSS_2_63") (pintype "bidirectional"))
      (node (ref "U1") (pin "GND") (pinfunction "GND_GND") (pintype "bidirectional"))
      (node (ref "U1") (pin "GND1") (pinfunction "GND_GND1") (pintype "bidirectional"))
    )
    (net (code "9") (name "I2C2_SCL") (class "Default")
      (node (ref "R11") (pin "1") (pinfunction "1_1") (pintype "passive"))
      (node (ref "U$12") (pin "2") (pinfunction "SCL_2") (pintype "bidirectional"))
      (node (ref "U$9") (pin "29") (pinfunction "PB10/I2C2_SCL(5T)_29") (pintype "bidirectional"))
    )
    (net (code "10") (name "I2C2_SDA") (class "Default")
      (node (ref "R12") (pin "1") (pinfunction "1_1") (pintype "passive"))
      (node (ref "U$12") (pin "3") (pinfunction "SDA_3") (pintype "bidirectional"))
      (node (ref "U$9") (pin "30") (pinfunction "PB11/I2C2_SDA(5T)_30") (pintype "bidirectional"))
    )
    (net (code "11") (name "I2C3_SCL") (class "Default")
      (node (ref "R41") (pin "2") (pinfunction "2_2") (pintype "passive"))
      (node (ref "U$13") (pin "P$18") (pinfunction "18.D0_P$18") (pintype "bidirectional"))
      (node (ref "U$9") (pin "41") (pinfunction "PA8/TIM1_CH1(5T)_41") (pintype "bidirectional"))
    )
    (net (code "12") (name "I2C3_SDA") (class "Default")
      (node (ref "R40") (pin "1") (pinfunction "1_1") (pintype "passive"))
      (node (ref "U$13") (pin "P$19") (pinfunction "19.D1_P$19") (pintype "bidirectional"))
      (node (ref "U$13") (pin "P$20") (pinfunction "20.D2_P$20") (pintype "bidirectional"))
      (node (ref "U$9") (pin "40") (pinfunction "PC9/TIM3_CH4/TIM8_CH4(5T)_40") (pintype "bidirectional"))
    )
    (net (code "13") (name "INT_EXTI12") (class "Default")
      (node (ref "R13") (pin "1") (pinfunction "1_1") (pintype "passive"))
      (node (ref "U$12") (pin "13") (pinfunction "INT_13") (pintype "bidirectional"))
      (node (ref "U$9") (pin "33") (pinfunction "PB12(5T)_33") (pintype "bidirectional"))
    )
    (net (code "14") (name "LED1") (class "Default")
      (node (ref "R46") (pin "2") (pinfunction "2_2") (pintype "passive"))
      (node (ref "U$9") (pin "53") (pinfunction "PC12(5T)_53") (pintype "bidirectional"))
    )
    (net (code "15") (name "LED2") (class "Default")
      (node (ref "R4") (pin "2") (pinfunction "2_2") (pintype "passive"))
      (node (ref "U$9") (pin "2") (pinfunction "PC13(5T)_2") (pintype "bidirectional"))
    )
    (net (code "16") (name "L_ARM") (class "Default")
      (node (ref "PAD2") (pin "1") (pinfunction "P_1") (pintype "passive"))
      (node (ref "R1") (pin "2") (pinfunction "WIPER_2") (pintype "passive"))
      (node (ref "U$10") (pin "P$1") (pinfunction "RECEIVE_P$1") (pintype "bidirectional"))
      (node (ref "U$10") (pin "P$2") (pinfunction "RES_P$2") (pintype "bidirectional"))
    )
    (net (code "17") (name "MCU_3V3") (class "Default")
      (node (ref "C10") (pin "2") (pinfunction "2_2") (pintype "passive"))
      (node (ref "C11") (pin "2") (pinfunction "2_2") (pintype "passive"))
      (node (ref "C23") (pin "2") (pinfunction "2_2") (pintype "passive"))
      (node (ref "C8") (pin "2") (pinfunction "2_2") (pintype "passive"))
      (node (ref "C9") (pin "2") (pinfunction "2_2") (pintype "passive"))
      (node (ref "D1") (pin "1") (pinfunction "C_1") (pintype "passive"))
      (node (ref "IC4") (pin "3") (pinfunction "IN_3") (pintype "input"))
      (node (ref "R11") (pin "2") (pinfunction "2_2") (pintype "passive"))
      (node (ref "R12") (pin "2") (pinfunction "2_2") (pintype "passive"))
      (node (ref "R13") (pin "2") (pinfunction "2_2") (pintype "passive"))
      (node (ref "R19") (pin "1") (pinfunction "1_1") (pintype "passive"))
      (node (ref "R40") (pin "2") (pinfunction "2_2") (pintype "passive"))
      (node (ref "R41") (pin "1") (pinfunction "1_1") (pintype "passive"))
      (node (ref "R45") (pin "1") (pinfunction "1_1") (pintype "passive"))
      (node (ref "R6") (pin "1") (pinfunction "1_1") (pintype "passive"))
      (node (ref "R7") (pin "2") (pinfunction "2_2") (pintype "passive"))
      (node (ref "R8") (pin "2") (pinfunction "2_2") (pintype "passive"))
      (node (ref "U$12") (pin "10") (pinfunction "IR_LED+_10") (pintype "bidirectional"))
      (node (ref "U$12") (pin "9") (pinfunction "R_LED+_9") (pintype "bidirectional"))
      (node (ref "U$3") (pin "1") (pinfunction "1.IN_1") (pintype "bidirectional"))
      (node (ref "U$5") (pin "8") (pinfunction "8.+VS_8") (pintype "bidirectional"))
      (node (ref "U$9") (pin "1") (pinfunction "VBAT_1") (pintype "bidirectional"))
      (node (ref "U$9") (pin "19") (pinfunction "VDD_1_19") (pintype "bidirectional"))
      (node (ref "U$9") (pin "32") (pinfunction "VDD_2_32") (pintype "bidirectional"))
      (node (ref "U$9") (pin "48") (pinfunction "VDD_3_48") (pintype "bidirectional"))
      (node (ref "U$9") (pin "64") (pinfunction "VDD_4_64") (pintype "bidirectional"))
      (node (ref "U4") (pin "4") (pinfunction "+V_4") (pintype "power_in"))
      (node (ref "U5") (pin "4") (pinfunction "+V_4") (pintype "power_in"))
    )
    (net (code "18") (name "NRST") (class "Default")
      (node (ref "C22") (pin "1") (pinfunction "1_1") (pintype "passive"))
      (node (ref "R7") (pin "1") (pinfunction "1_1") (pintype "passive"))
      (node (ref "S1") (pin "1") (pinfunction "1_1") (pintype "passive"))
      (node (ref "S1") (pin "2") (pinfunction "2_2") (pintype "passive"))
      (node (ref "U$9") (pin "7") (pinfunction "NRST_7") (pintype "bidirectional"))
    )
    (net (code "19") (name "Net-(C27-Pad1)") (class "Default")
      (node (ref "C27") (pin "1") (pinfunction "1_1") (pintype "passive"))
      (node (ref "C28") (pin "1") (pinfunction "1_1") (pintype "passive"))
      (node (ref "R23") (pin "1") (pinfunction "1_1") (pintype "passive"))
    )
    (net (code "20") (name "Net-(C28-Pad2)") (class "Default")
      (node (ref "C28") (pin "2") (pinfunction "2_2") (pintype "passive"))
      (node (ref "C30") (pin "1") (pinfunction "1_1") (pintype "passive"))
      (node (ref "R25") (pin "1") (pinfunction "1_1") (pintype "passive"))
    )
    (net (code "21") (name "Net-(C32-Pad1)") (class "Default")
      (node (ref "C32") (pin "1") (pinfunction "1_1") (pintype "passive"))
      (node (ref "R30") (pin "2") (pinfunction "2_2") (pintype "passive"))
      (node (ref "R31") (pin "1") (pinfunction "1_1") (pintype "passive"))
    )
    (net (code "22") (name "Net-(C33-Pad1)") (class "Default")
      (node (ref "C33") (pin "1") (pinfunction "1_1") (pintype "passive"))
      (node (ref "C34") (pin "2") (pinfunction "2_2") (pintype "passive"))
      (node (ref "R36") (pin "2") (pinfunction "2_2") (pintype "passive"))
    )
    (net (code "23") (name "Net-(C35-Pad1)") (class "Default")
      (node (ref "C35") (pin "1") (pinfunction "1_1") (pintype "passive"))
      (node (ref "R34") (pin "2") (pinfunction "2_2") (pintype "passive"))
      (node (ref "R35") (pin "1") (pinfunction "1_1") (pintype "passive"))
    )
    (net (code "24") (name "Net-(C39-+)") (class "Default")
      (node (ref "BAT1") (pin "+") (pinfunction "+_+") (pintype "power_in"))
      (node (ref "C29") (pin "+") (pinfunction "+_+") (pintype "passive"))
      (node (ref "C39") (pin "A") (pinfunction "+_A") (pintype "passive"))
      (node (ref "R65") (pin "2") (pinfunction "2_2") (pintype "passive"))
      (node (ref "SW1") (pin "COM1") (pinfunction "COM1_COM1") (pintype "bidirectional"))
      (node (ref "U$6") (pin "5") (pinfunction "BAT_5") (pintype "bidirectional"))
    )
    (net (code "25") (name "Net-(D1-A)") (class "Default")
      (node (ref "C7") (pin "2") (pinfunction "2_2") (pintype "passive"))
      (node (ref "D1") (pin "2") (pinfunction "A_2") (pintype "passive"))
      (node (ref "IC1") (pin "5") (pinfunction "VO_5") (pintype "output"))
    )
    (net (code "26") (name "Net-(D2-PadA)") (class "Default")
      (node (ref "D2") (pin "A") (pinfunction "A_A") (pintype "passive"))
      (node (ref "R4") (pin "1") (pinfunction "1_1") (pintype "passive"))
    )
    (net (code "27") (name "Net-(D3-PadA)") (class "Default")
      (node (ref "D3") (pin "A") (pinfunction "A_A") (pintype "passive"))
      (node (ref "R46") (pin "1") (pinfunction "1_1") (pintype "passive"))
    )
    (net (code "28") (name "Net-(D5-PadC)") (class "Default")
      (node (ref "D5") (pin "C") (pinfunction "C_C") (pintype "passive"))
      (node (ref "R64") (pin "2") (pinfunction "2_2") (pintype "passive"))
    )
    (net (code "29") (name "Net-(D6-PadC)") (class "Default")
      (node (ref "D6") (pin "C") (pinfunction "C_C") (pintype "passive"))
      (node (ref "R63") (pin "2") (pinfunction "2_2") (pintype "passive"))
    )
    (net (code "30") (name "Net-(IC1-BYPASS)") (class "Default")
      (node (ref "C6") (pin "2") (pinfunction "2_2") (pintype "passive"))
      (node (ref "IC1") (pin "4") (pinfunction "BYPASS_4") (pintype "passive"))
    )
    (net (code "31") (name "Net-(R1-CCW)") (class "Default")
      (node (ref "R1") (pin "1") (pinfunction "CCW_1") (pintype "passive"))
      (node (ref "R22") (pin "2") (pinfunction "2_2") (pintype "passive"))
      (node (ref "U$5") (pin "1") (pinfunction "1.-IN_1") (pintype "bidirectional"))
    )
    (net (code "32") (name "Net-(R2-CCW)") (class "Default")
      (node (ref "R2") (pin "1") (pinfunction "CCW_1") (pintype "passive"))
      (node (ref "R21") (pin "2") (pinfunction "2_2") (pintype "passive"))
      (node (ref "U$5") (pin "4") (pinfunction "4.+IN_4") (pintype "bidirectional"))
    )
    (net (code "33") (name "Net-(R3-CW)") (class "Default")
      (node (ref "R3") (pin "3") (pinfunction "CW_3") (pintype "passive"))
      (node (ref "U$5") (pin "3") (pinfunction "3.RG_3") (pintype "bidirectional"))
    )
    (net (code "34") (name "Net-(R3-WIPER)") (class "Default")
      (node (ref "R3") (pin "2") (pinfunction "WIPER_2") (pintype "passive"))
      (node (ref "U$5") (pin "2") (pinfunction "2.RG_2") (pintype "bidirectional"))
    )
    (net (code "35") (name "Net-(T1A-D)") (class "Default")
      (node (ref "T1") (pin "1") (pinfunction "D_1") (pintype "passive"))
      (node (ref "T1") (pin "8") (pinfunction "D_8") (pintype "passive"))
    )
    (net (code "36") (name "Net-(T1A-G)") (class "Default")
      (node (ref "T1") (pin "4") (pinfunction "G_4") (pintype "passive"))
      (node (ref "U$7") (pin "1") (pinfunction "0D_1") (pintype "bidirectional"))
    )
    (net (code "37") (name "Net-(T1B-G)") (class "Default")
      (node (ref "T1") (pin "5") (pinfunction "G_5") (pintype "passive"))
      (node (ref "U$7") (pin "3") (pinfunction "0C_3") (pintype "bidirectional"))
    )
    (net (code "38") (name "Net-(U$5-6.REF)") (class "Default")
      (node (ref "C4") (pin "2") (pinfunction "2_2") (pintype "passive"))
      (node (ref "U$5") (pin "6") (pinfunction "6.REF_6") (pintype "bidirectional"))
      (node (ref "U4") (pin "1") (pinfunction "OUT1_1") (pintype "output"))
    )
    (net (code "39") (name "Net-(U$5-7.VOUT)") (class "Default")
      (node (ref "R16") (pin "1") (pinfunction "1_1") (pintype "passive"))
      (node (ref "R17") (pin "2") (pinfunction "2_2") (pintype "passive"))
      (node (ref "U$5") (pin "7") (pinfunction "7.VOUT_7") (pintype "bidirectional"))
    )
    (net (code "40") (name "Net-(U$6-PROG)") (class "Default")
      (node (ref "R62") (pin "2") (pinfunction "2_2") (pintype "passive"))
      (node (ref "U$6") (pin "2") (pinfunction "PROG_2") (pintype "bidirectional"))
    )
    (net (code "41") (name "Net-(U$6-~{CHRG})") (class "Default")
      (node (ref "R63") (pin "1") (pinfunction "1_1") (pintype "passive"))
      (node (ref "U$6") (pin "7") (pinfunction "~{CHRG}_7") (pintype "bidirectional"))
    )
    (net (code "42") (name "Net-(U$6-~{STDBY})") (class "Default")
      (node (ref "R64") (pin "1") (pinfunction "1_1") (pintype "passive"))
      (node (ref "U$6") (pin "6") (pinfunction "~{STDBY}_6") (pintype "bidirectional"))
    )
    (net (code "43") (name "Net-(U$7-CS)") (class "Default")
      (node (ref "R66") (pin "2") (pinfunction "2_2") (pintype "passive"))
      (node (ref "U$7") (pin "2") (pinfunction "CS_2") (pintype "bidirectional"))
    )
    (net (code "44") (name "Net-(U$7-GND)") (class "Default")
      (node (ref "BAT1") (pin "-") (pinfunction "-_-") (pintype "power_in"))
      (node (ref "C29") (pin "-") (pinfunction "-_-") (pintype "passive"))
      (node (ref "C40") (pin "2") (pinfunction "2_2") (pintype "passive"))
      (node (ref "T1") (pin "2") (pinfunction "S_2") (pintype "passive"))
      (node (ref "T1") (pin "3") (pinfunction "S_3") (pintype "passive"))
      (node (ref "U$7") (pin "6") (pinfunction "GND_6") (pintype "bidirectional"))
    )
    (net (code "45") (name "Net-(U$7-VCC)") (class "Default")
      (node (ref "C40") (pin "1") (pinfunction "1_1") (pintype "passive"))
      (node (ref "R65") (pin "1") (pinfunction "1_1") (pintype "passive"))
      (node (ref "U$7") (pin "5") (pinfunction "VCC_5") (pintype "bidirectional"))
    )
    (net (code "46") (name "Net-(U$9-VCAP_1)") (class "Default")
      (node (ref "C17") (pin "1") (pinfunction "1_1") (pintype "passive"))
      (node (ref "U$9") (pin "31") (pinfunction "VCAP_1_31") (pintype "bidirectional"))
    )
    (net (code "47") (name "Net-(U$9-VCAP_2)") (class "Default")
      (node (ref "C16") (pin "1") (pinfunction "1_1") (pintype "passive"))
      (node (ref "U$9") (pin "47") (pinfunction "VCAP_2_47") (pintype "bidirectional"))
    )
    (net (code "48") (name "Net-(U$13-2.C2P)") (class "Default")
      (node (ref "C2") (pin "2") (pinfunction "2_2") (pintype "passive"))
      (node (ref "U$13") (pin "P$2") (pinfunction "2.C2P_P$2") (pintype "bidirectional"))
    )
    (net (code "49") (name "Net-(U$13-3.C2N)") (class "Default")
      (node (ref "C2") (pin "1") (pinfunction "1_1") (pintype "passive"))
      (node (ref "U$13") (pin "P$3") (pinfunction "3.C2N_P$3") (pintype "bidirectional"))
    )
    (net (code "50") (name "Net-(U$13-4.C1P)") (class "Default")
      (node (ref "C36") (pin "2") (pinfunction "2_2") (pintype "passive"))
      (node (ref "U$13") (pin "P$4") (pinfunction "4.C1P_P$4") (pintype "bidirectional"))
    )
    (net (code "51") (name "Net-(U$13-5.C1N)") (class "Default")
      (node (ref "C36") (pin "1") (pinfunction "1_1") (pintype "passive"))
      (node (ref "U$13") (pin "P$5") (pinfunction "5.C1N_P$5") (pintype "bidirectional"))
    )
    (net (code "52") (name "Net-(U$13-14.RES#)") (class "Default")
      (node (ref "C1") (pin "2") (pinfunction "2_2") (pintype "passive"))
      (node (ref "R38") (pin "2") (pinfunction "2_2") (pintype "passive"))
      (node (ref "U$13") (pin "P$14") (pinfunction "14.RES#_P$14") (pintype "bidirectional"))
    )
    (net (code "53") (name "Net-(U$13-26.IREF)") (class "Default")
      (node (ref "R39") (pin "1") (pinfunction "1_1") (pintype "passive"))
      (node (ref "U$13") (pin "P$26") (pinfunction "26.IREF_P$26") (pintype "bidirectional"))
    )
    (net (code "54") (name "Net-(U$13-27.VCOMH)") (class "Default")
      (node (ref "C3") (pin "2") (pinfunction "2_2") (pintype "passive"))
      (node (ref "U$13") (pin "P$27") (pinfunction "27.VCOMH_P$27") (pintype "bidirectional"))
    )
    (net (code "55") (name "Net-(U$13-28.VCC)") (class "Default")
      (node (ref "C37") (pin "2") (pinfunction "2_2") (pintype "passive"))
      (node (ref "U$13") (pin "P$28") (pinfunction "28.VCC_P$28") (pintype "bidirectional"))
    )
    (net (code "56") (name "Net-(U$15-1.IN)") (class "Default")
      (node (ref "U$15") (pin "1") (pinfunction "1.IN_1") (pintype "bidirectional"))
      (node (ref "U1") (pin "VBUS1") (pinfunction "VBUS_VBUS1") (pintype "bidirectional"))
    )
    (net (code "57") (name "Net-(U$15-2.OUT)") (class "Default")
      (node (ref "R42") (pin "2") (pinfunction "2_2") (pintype "passive"))
      (node (ref "U$15") (pin "2") (pinfunction "2.OUT_2") (pintype "bidirectional"))
    )
    (net (code "58") (name "Net-(U1-D+)") (class "Default")
      (node (ref "R15") (pin "2") (pinfunction "2_2") (pintype "passive"))
      (node (ref "U1") (pin "D+1") (pinfunction "D+_D+1") (pintype "bidirectional"))
    )
    (net (code "59") (name "Net-(U1-D-)") (class "Default")
      (node (ref "R14") (pin "2") (pinfunction "2_2") (pintype "passive"))
      (node (ref "U1") (pin "D-1") (pinfunction "D-_D-1") (pintype "bidirectional"))
    )
    (net (code "60") (name "Net-(U1-USBID)") (class "Default")
      (node (ref "R43") (pin "2") (pinfunction "2_2") (pintype "passive"))
      (node (ref "U1") (pin "ID1") (pinfunction "USBID_ID1") (pintype "bidirectional"))
    )
    (net (code "61") (name "Net-(U4A-+IN1)") (class "Default")
      (node (ref "C26") (pin "1") (pinfunction "1_1") (pintype "passive"))
      (node (ref "R19") (pin "2") (pinfunction "2_2") (pintype "passive"))
      (node (ref "R20") (pin "1") (pinfunction "1_1") (pintype "passive"))
      (node (ref "R21") (pin "1") (pinfunction "1_1") (pintype "passive"))
      (node (ref "R22") (pin "1") (pinfunction "1_1") (pintype "passive"))
      (node (ref "U4") (pin "3") (pinfunction "+IN1_3") (pintype "input"))
      (node (ref "U4") (pin "5") (pinfunction "+IN2_5") (pintype "input"))
    )
    (net (code "62") (name "Net-(U4A--IN1)") (class "Default")
      (node (ref "C4") (pin "1") (pinfunction "1_1") (pintype "passive"))
      (node (ref "R16") (pin "2") (pinfunction "2_2") (pintype "passive"))
      (node (ref "U4") (pin "2") (pinfunction "-IN1_2") (pintype "input"))
    )
    (net (code "63") (name "Net-(U4B--IN2)") (class "Default")
      (node (ref "C25") (pin "2") (pinfunction "2_2") (pintype "passive"))
      (node (ref "R17") (pin "1") (pinfunction "1_1") (pintype "passive"))
      (node (ref "R18") (pin "2") (pinfunction "2_2") (pintype "passive"))
      (node (ref "U4") (pin "6") (pinfunction "-IN2_6") (pintype "input"))
    )
    (net (code "64") (name "Net-(U4B-OUT2)") (class "Default")
      (node (ref "C25") (pin "1") (pinfunction "1_1") (pintype "passive"))
      (node (ref "R18") (pin "1") (pinfunction "1_1") (pintype "passive"))
      (node (ref "R23") (pin "2") (pinfunction "2_2") (pintype "passive"))
      (node (ref "U4") (pin "7") (pinfunction "OUT2_7") (pintype "output"))
    )
    (net (code "65") (name "Net-(U4C-+IN2)") (class "Default")
      (node (ref "R47") (pin "1") (pinfunction "1_1") (pintype "passive"))
      (node (ref "R48") (pin "2") (pinfunction "2_2") (pintype "passive"))
      (node (ref "U4") (pin "10") (pinfunction "+IN2_10") (pintype "input"))
    )
    (net (code "66") (name "Net-(U5A-+IN1)") (class "Default")
      (node (ref "C30") (pin "2") (pinfunction "2_2") (pintype "passive"))
      (node (ref "R24") (pin "1") (pinfunction "1_1") (pintype "passive"))
      (node (ref "U5") (pin "3") (pinfunction "+IN1_3") (pintype "input"))
    )
    (net (code "67") (name "Net-(U5A--IN1)") (class "Default")
      (node (ref "R26") (pin "2") (pinfunction "2_2") (pintype "passive"))
      (node (ref "R27") (pin "2") (pinfunction "2_2") (pintype "passive"))
      (node (ref "U5") (pin "2") (pinfunction "-IN1_2") (pintype "input"))
    )
    (net (code "68") (name "Net-(U5A-OUT1)") (class "Default")
      (node (ref "R25") (pin "2") (pinfunction "2_2") (pintype "passive"))
      (node (ref "R27") (pin "1") (pinfunction "1_1") (pintype "passive"))
      (node (ref "U5") (pin "1") (pinfunction "OUT1_1") (pintype "output"))
      (node (ref "U5") (pin "5") (pinfunction "+IN2_5") (pintype "input"))
    )
    (net (code "69") (name "Net-(U5B--IN2)") (class "Default")
      (node (ref "R28") (pin "2") (pinfunction "2_2") (pintype "passive"))
      (node (ref "R29") (pin "2") (pinfunction "2_2") (pintype "passive"))
      (node (ref "U5") (pin "6") (pinfunction "-IN2_6") (pintype "input"))
    )
    (net (code "70") (name "Net-(U5B-OUT2)") (class "Default")
      (node (ref "R29") (pin "1") (pinfunction "1_1") (pintype "passive"))
      (node (ref "R30") (pin "1") (pinfunction "1_1") (pintype "passive"))
      (node (ref "U5") (pin "7") (pinfunction "OUT2_7") (pintype "output"))
    )
    (net (code "71") (name "Net-(U5C-+IN2)") (class "Default")
      (node (ref "C31") (pin "1") (pinfunction "1_1") (pintype "passive"))
      (node (ref "R31") (pin "2") (pinfunction "2_2") (pintype "passive"))
      (node (ref "U5") (pin "10") (pinfunction "+IN2_10") (pintype "input"))
    )
    (net (code "72") (name "Net-(U5C--IN2)") (class "Default")
      (node (ref "R32") (pin "2") (pinfunction "2_2") (pintype "passive"))
      (node (ref "R33") (pin "1") (pinfunction "1_1") (pintype "passive"))
      (node (ref "U5") (pin "9") (pinfunction "-IN2_9") (pintype "input"))
    )
    (net (code "73") (name "Net-(U5C-OUT2)") (class "Default")
      (node (ref "C32") (pin "2") (pinfunction "2_2") (pintype "passive"))
      (node (ref "C34") (pin "1") (pinfunction "1_1") (pintype "passive"))
      (node (ref "R33") (pin "2") (pinfunction "2_2") (pintype "passive"))
      (node (ref "R34") (pin "1") (pinfunction "1_1") (pintype "passive"))
      (node (ref "U5") (pin "8") (pinfunction "OUT2_8") (pintype "output"))
    )
    (net (code "74") (name "Net-(U5D-+IN2)") (class "Default")
      (node (ref "C33") (pin "2") (pinfunction "2_2") (pintype "passive"))
      (node (ref "R35") (pin "2") (pinfunction "2_2") (pintype "passive"))
      (node (ref "U5") (pin "12") (pinfunction "+IN2_12") (pintype "input"))
    )
    (net (code "75") (name "Net-(U5D--IN2)") (class "Default")
      (node (ref "R37") (pin "1") (pinfunction "1_1") (pintype "passive"))
      (node (ref "U5") (pin "13") (pinfunction "-IN2_13") (pintype "input"))
    )
    (net (code "76") (name "Net-(U5D-OUT2)") (class "Default")
      (node (ref "C35") (pin "2") (pinfunction "2_2") (pintype "passive"))
      (node (ref "R37") (pin "2") (pinfunction "2_2") (pintype "passive"))
      (node (ref "R49") (pin "1") (pinfunction "1_1") (pintype "passive"))
      (node (ref "U5") (pin "14") (pinfunction "OUT2_14") (pintype "output"))
    )
    (net (code "77") (name "OSC32_IN") (class "Default")
      (node (ref "C21") (pin "2") (pinfunction "2_2") (pintype "passive"))
      (node (ref "U$4") (pin "1") (pinfunction "1.XIN_1") (pintype "bidirectional"))
      (node (ref "U$9") (pin "3") (pinfunction "PC14/OSC32_IN(5T)_3") (pintype "bidirectional"))
    )
    (net (code "78") (name "OSC32_OUT") (class "Default")
      (node (ref "C20") (pin "2") (pinfunction "2_2") (pintype "passive"))
      (node (ref "U$4") (pin "2") (pinfunction "2.XIN_2") (pintype "bidirectional"))
      (node (ref "U$9") (pin "4") (pinfunction "PC15/OSC32_OUT(5T)_4") (pintype "bidirectional"))
    )
    (net (code "79") (name "OSC_IN") (class "Default")
      (node (ref "C19") (pin "2") (pinfunction "2_2") (pintype "passive"))
      (node (ref "U$2") (pin "1") (pinfunction "1.XIN_1") (pintype "bidirectional"))
      (node (ref "U$9") (pin "5") (pinfunction "PH0/OSC_IN(5T)_5") (pintype "bidirectional"))
    )
    (net (code "80") (name "OSC_OUT") (class "Default")
      (node (ref "C18") (pin "2") (pinfunction "2_2") (pintype "passive"))
      (node (ref "U$2") (pin "2") (pinfunction "2.XOUT_2") (pintype "bidirectional"))
      (node (ref "U$9") (pin "6") (pinfunction "PH1/OSC_OUT(5T)_6") (pintype "bidirectional"))
    )
    (net (code "81") (name "OTG_FS_DM") (class "Default")
      (node (ref "R14") (pin "1") (pinfunction "1_1") (pintype "passive"))
      (node (ref "U$9") (pin "44") (pinfunction "PA11/TIM1_CH4/CANRX/USBDM(5T)_44") (pintype "bidirectional"))
    )
    (net (code "82") (name "OTG_FS_DP") (class "Default")
      (node (ref "R15") (pin "1") (pinfunction "1_1") (pintype "passive"))
      (node (ref "U$9") (pin "45") (pinfunction "PA12/CANTX/USBDP(5T)_45") (pintype "bidirectional"))
    )
    (net (code "83") (name "OTG_FS_ID") (class "Default")
      (node (ref "R43") (pin "1") (pinfunction "1_1") (pintype "passive"))
      (node (ref "U$9") (pin "43") (pinfunction "PA10/TIM1_CH3/USART1_RX(5T)_43") (pintype "bidirectional"))
    )
    (net (code "84") (name "R_ARM") (class "Default")
      (node (ref "PAD1") (pin "1") (pinfunction "P_1") (pintype "passive"))
      (node (ref "R2") (pin "2") (pinfunction "WIPER_2") (pintype "passive"))
      (node (ref "U$8") (pin "P$1") (pinfunction "RECEIVE_P$1") (pintype "bidirectional"))
      (node (ref "U$8") (pin "P$2") (pinfunction "RES_P$2") (pintype "bidirectional"))
    )
    (net (code "85") (name "SWTCK") (class "Default")
      (node (ref "JP2") (pin "3") (pinfunction "3_3") (pintype "passive"))
      (node (ref "U$9") (pin "49") (pinfunction "PA14/JTCK-SWCLK(5T)_49") (pintype "bidirectional"))
    )
    (net (code "86") (name "SWTDIO") (class "Default")
      (node (ref "JP2") (pin "4") (pinfunction "4_4") (pintype "passive"))
      (node (ref "U$9") (pin "46") (pinfunction "PA13/JTMS-SWDAT(5T)_46") (pintype "bidirectional"))
    )
    (net (code "87") (name "VBUS") (class "Default")
      (node (ref "C38") (pin "A") (pinfunction "+_A") (pintype "passive"))
      (node (ref "D5") (pin "A") (pinfunction "A_A") (pintype "passive"))
      (node (ref "D6") (pin "A") (pinfunction "A_A") (pintype "passive"))
      (node (ref "R42") (pin "1") (pinfunction "1_1") (pintype "passive"))
      (node (ref "U$6") (pin "4") (pinfunction "VCC_4") (pintype "bidirectional"))
      (node (ref "U$6") (pin "8") (pinfunction "CE_8") (pintype "bidirectional"))
      (node (ref "U$9") (pin "42") (pinfunction "PA9/TIM1_CH2/USART1_TX(5T)_42") (pintype "bidirectional"))
    )
    (net (code "88") (name "VCC") (class "Default")
      (node (ref "C5") (pin "2") (pinfunction "2_2") (pintype "passive"))
      (node (ref "IC1") (pin "1") (pinfunction "VIN_1") (pintype "input"))
      (node (ref "IC1") (pin "3") (pinfunction "VINH_3") (pintype "input"))
      (node (ref "JP2") (pin "1") (pinfunction "1_1") (pintype "passive"))
      (node (ref "R38") (pin "1") (pinfunction "1_1") (pintype "passive"))
      (node (ref "R47") (pin "2") (pinfunction "2_2") (pintype "passive"))
      (node (ref "SW1") (pin "CH1A") (pinfunction "CH1A_CH1A") (pintype "bidirectional"))
      (node (ref "U$13") (pin "P$11") (pinfunction "11.BS1_P$11") (pintype "bidirectional"))
      (node (ref "U$13") (pin "P$6") (pinfunction "6.VBAT_P$6") (pintype "bidirectional"))
      (node (ref "U$13") (pin "P$9") (pinfunction "9.VDD_P$9") (pintype "bidirectional"))
    )
    (net (code "89") (name "VDDA") (class "Default")
      (node (ref "C12") (pin "2") (pinfunction "2_2") (pintype "passive"))
      (node (ref "C13") (pin "2") (pinfunction "2_2") (pintype "passive"))
      (node (ref "C14") (pin "2") (pinfunction "2_2") (pintype "passive"))
      (node (ref "C15") (pin "2") (pinfunction "2_2") (pintype "passive"))
      (node (ref "U$3") (pin "2") (pinfunction "2.OUT_2") (pintype "bidirectional"))
      (node (ref "U$9") (pin "13") (pinfunction "VDDA_13") (pintype "bidirectional"))
    )
    (net (code "90") (name "unconnected-(R1-CW-Pad3)") (class "Default")
      (node (ref "R1") (pin "3") (pinfunction "CW_3") (pintype "passive"))
    )
    (net (code "91") (name "unconnected-(R2-CW-Pad3)") (class "Default")
      (node (ref "R2") (pin "3") (pinfunction "CW_3") (pintype "passive"))
    )
    (net (code "92") (name "unconnected-(R3-CCW-Pad1)") (class "Default")
      (node (ref "R3") (pin "1") (pinfunction "CCW_1") (pintype "passive"))
    )
    (net (code "93") (name "unconnected-(SW1-PadCH1B)") (class "Default")
      (node (ref "SW1") (pin "CH1B") (pinfunction "CH1B_CH1B") (pintype "bidirectional"))
    )
    (net (code "94") (name "unconnected-(SW1-PadCH2A)") (class "Default")
      (node (ref "SW1") (pin "CH2A") (pinfunction "CH2A_CH2A") (pintype "bidirectional"))
    )
    (net (code "95") (name "unconnected-(SW1-PadCH2B)") (class "Default")
      (node (ref "SW1") (pin "CH2B") (pinfunction "CH2B_CH2B") (pintype "bidirectional"))
    )
    (net (code "96") (name "unconnected-(SW1-PadCOM2)") (class "Default")
      (node (ref "SW1") (pin "COM2") (pinfunction "COM2_COM2") (pintype "bidirectional"))
    )
    (net (code "97") (name "unconnected-(U$7-TD-Pad4)") (class "Default")
      (node (ref "U$7") (pin "4") (pinfunction "TD_4") (pintype "bidirectional"))
    )
    (net (code "98") (name "unconnected-(U$9-PA1{slash}ADC123_IN1(5T)-Pad15)") (class "Default")
      (node (ref "U$9") (pin "15") (pinfunction "PA1/ADC123_IN1(5T)_15") (pintype "bidirectional"))
    )
    (net (code "99") (name "unconnected-(U$9-PA2{slash}ADC123_IN2(5T)-Pad16)") (class "Default")
      (node (ref "U$9") (pin "16") (pinfunction "PA2/ADC123_IN2(5T)_16") (pintype "bidirectional"))
    )
    (net (code "100") (name "unconnected-(U$9-PA3{slash}ADC123_IN3(5T)-Pad17)") (class "Default")
      (node (ref "U$9") (pin "17") (pinfunction "PA3/ADC123_IN3(5T)_17") (pintype "bidirectional"))
    )
    (net (code "101") (name "unconnected-(U$9-PA4{slash}ADC12_IN4-Pad20)") (class "Default")
      (node (ref "U$9") (pin "20") (pinfunction "PA4/ADC12_IN4_20") (pintype "bidirectional"))
    )
    (net (code "102") (name "unconnected-(U$9-PA5{slash}ADC12_IN5-Pad21)") (class "Default")
      (node (ref "U$9") (pin "21") (pinfunction "PA5/ADC12_IN5_21") (pintype "bidirectional"))
    )
    (net (code "103") (name "unconnected-(U$9-PA6{slash}ADC12_IN6(5T)-Pad22)") (class "Default")
      (node (ref "U$9") (pin "22") (pinfunction "PA6/ADC12_IN6(5T)_22") (pintype "bidirectional"))
    )
    (net (code "104") (name "unconnected-(U$9-PA7{slash}TIM1_CH1N{slash}ADC12_IN7(FT)-Pad23)") (class "Default")
      (node (ref "U$9") (pin "23") (pinfunction "PA7/TIM1_CH1N/ADC12_IN7(FT)_23") (pintype "bidirectional"))
    )
    (net (code "105") (name "unconnected-(U$9-PA15{slash}JTDI(5T)-Pad50)") (class "Default")
      (node (ref "U$9") (pin "50") (pinfunction "PA15/JTDI(5T)_50") (pintype "bidirectional"))
    )
    (net (code "106") (name "unconnected-(U$9-PB0{slash}TIM1_CH2N{slash}ADC12_IN8(5T)-Pad26)") (class "Default")
      (node (ref "U$9") (pin "26") (pinfunction "PB0/TIM1_CH2N/ADC12_IN8(5T)_26") (pintype "bidirectional"))
    )
    (net (code "107") (name "unconnected-(U$9-PB1{slash}TIM1_CH3N{slash}ADC12_IN9(5T)-Pad27)") (class "Default")
      (node (ref "U$9") (pin "27") (pinfunction "PB1/TIM1_CH3N/ADC12_IN9(5T)_27") (pintype "bidirectional"))
    )
    (net (code "108") (name "unconnected-(U$9-PB3{slash}JTDO(5T)-Pad55)") (class "Default")
      (node (ref "U$9") (pin "55") (pinfunction "PB3/JTDO(5T)_55") (pintype "bidirectional"))
    )
    (net (code "109") (name "unconnected-(U$9-PB4{slash}JNTRST(5T)-Pad56)") (class "Default")
      (node (ref "U$9") (pin "56") (pinfunction "PB4/JNTRST(5T)_56") (pintype "bidirectional"))
    )
    (net (code "110") (name "unconnected-(U$9-PB5(5T)-Pad57)") (class "Default")
      (node (ref "U$9") (pin "57") (pinfunction "PB5(5T)_57") (pintype "bidirectional"))
    )
    (net (code "111") (name "unconnected-(U$9-PB6{slash}I2C1_SCL{slash}USART1_TX{slash}TIM4_CH1(5T)-Pad58)") (class "Default")
      (node (ref "U$9") (pin "58") (pinfunction "PB6/I2C1_SCL/USART1_TX/TIM4_CH1(5T)_58") (pintype "bidirectional"))
    )
    (net (code "112") (name "unconnected-(U$9-PB7{slash}I2C1_SDA{slash}USART1_RX{slash}TIM4_CH2(5T)-Pad59)") (class "Default")
      (node (ref "U$9") (pin "59") (pinfunction "PB7/I2C1_SDA/USART1_RX/TIM4_CH2(5T)_59") (pintype "bidirectional"))
    )
    (net (code "113") (name "unconnected-(U$9-PB8{slash}TIM10_CH1{slash}TIM4_CH3(5T)-Pad61)") (class "Default")
      (node (ref "U$9") (pin "61") (pinfunction "PB8/TIM10_CH1/TIM4_CH3(5T)_61") (pintype "bidirectional"))
    )
    (net (code "114") (name "unconnected-(U$9-PB9{slash}TIM11_CH1{slash}TIM4_CH4(5T)-Pad62)") (class "Default")
      (node (ref "U$9") (pin "62") (pinfunction "PB9/TIM11_CH1/TIM4_CH4(5T)_62") (pintype "bidirectional"))
    )
    (net (code "115") (name "unconnected-(U$9-PB13{slash}SPI2_SCK(5T)-Pad34)") (class "Default")
      (node (ref "U$9") (pin "34") (pinfunction "PB13/SPI2_SCK(5T)_34") (pintype "bidirectional"))
    )
    (net (code "116") (name "unconnected-(U$9-PB14{slash}SPI2_MISO(5T)-Pad35)") (class "Default")
      (node (ref "U$9") (pin "35") (pinfunction "PB14/SPI2_MISO(5T)_35") (pintype "bidirectional"))
    )
    (net (code "117") (name "unconnected-(U$9-PB15{slash}SPI2_MOSI(5T)-Pad36)") (class "Default")
      (node (ref "U$9") (pin "36") (pinfunction "PB15/SPI2_MOSI(5T)_36") (pintype "bidirectional"))
    )
    (net (code "118") (name "unconnected-(U$9-PC2{slash}ADC123_IN12(5T)-Pad10)") (class "Default")
      (node (ref "U$9") (pin "10") (pinfunction "PC2/ADC123_IN12(5T)_10") (pintype "bidirectional"))
    )
    (net (code "119") (name "unconnected-(U$9-PC3{slash}ADC123_IN13(5T)-Pad11)") (class "Default")
      (node (ref "U$9") (pin "11") (pinfunction "PC3/ADC123_IN13(5T)_11") (pintype "bidirectional"))
    )
    (net (code "120") (name "unconnected-(U$9-PC4{slash}ADC12_IN14-Pad24)") (class "Default")
      (node (ref "U$9") (pin "24") (pinfunction "PC4/ADC12_IN14_24") (pintype "bidirectional"))
    )
    (net (code "121") (name "unconnected-(U$9-PC5{slash}ADC12_IN15-Pad25)") (class "Default")
      (node (ref "U$9") (pin "25") (pinfunction "PC5/ADC12_IN15_25") (pintype "bidirectional"))
    )
    (net (code "122") (name "unconnected-(U$9-PC6{slash}TIM3_CH1{slash}TIM_CH1{slash}USART6_TX(5T)-Pad37)") (class "Default")
      (node (ref "U$9") (pin "37") (pinfunction "PC6/TIM3_CH1/TIM_CH1/USART6_TX(5T)_37") (pintype "bidirectional"))
    )
    (net (code "123") (name "unconnected-(U$9-PC7{slash}TIM3_CH2{slash}TIM8_CH2{slash}USART6_RX(5T)-Pad38)") (class "Default")
      (node (ref "U$9") (pin "38") (pinfunction "PC7/TIM3_CH2/TIM8_CH2/USART6_RX(5T)_38") (pintype "bidirectional"))
    )
    (net (code "124") (name "unconnected-(U$9-PC8{slash}TIM3_CH3{slash}TIM8_CH3(5T)-Pad39)") (class "Default")
      (node (ref "U$9") (pin "39") (pinfunction "PC8/TIM3_CH3/TIM8_CH3(5T)_39") (pintype "bidirectional"))
    )
    (net (code "125") (name "unconnected-(U$9-PC10(5T)-Pad51)") (class "Default")
      (node (ref "U$9") (pin "51") (pinfunction "PC10(5T)_51") (pintype "bidirectional"))
    )
    (net (code "126") (name "unconnected-(U$9-PC11(5T)-Pad52)") (class "Default")
      (node (ref "U$9") (pin "52") (pinfunction "PC11(5T)_52") (pintype "bidirectional"))
    )
    (net (code "127") (name "unconnected-(U$9-PD2{slash}TIM3_ETR(5T)-Pad54)") (class "Default")
      (node (ref "U$9") (pin "54") (pinfunction "PD2/TIM3_ETR(5T)_54") (pintype "bidirectional"))
    )
    (net (code "128") (name "unconnected-(U$12-IR_DRV-Pad5)") (class "Default")
      (node (ref "U$12") (pin "5") (pinfunction "IR_DRV_5") (pintype "bidirectional"))
    )
    (net (code "129") (name "unconnected-(U$12-R_DRV-Pad6)") (class "Default")
      (node (ref "U$12") (pin "6") (pinfunction "R_DRV_6") (pintype "bidirectional"))
    )
    (net (code "130") (name "unconnected-(U$13-1.NC(GND)-PadP$1)") (class "Default")
      (node (ref "U$13") (pin "P$1") (pinfunction "1.NC(GND)_P$1") (pintype "bidirectional"))
    )
    (net (code "131") (name "unconnected-(U$13-7.NC-PadP$7)") (class "Default")
      (node (ref "U$13") (pin "P$7") (pinfunction "7.NC_P$7") (pintype "bidirectional"))
    )
    (net (code "132") (name "unconnected-(U$13-30.NC(GND)-PadP$30)") (class "Default")
      (node (ref "U$13") (pin "P$30") (pinfunction "30.NC(GND)_P$30") (pintype "bidirectional"))
    )
    (net (code "133") (name "unconnected-(U4D-+IN2-Pad12)") (class "Default")
      (node (ref "U4") (pin "12") (pinfunction "+IN2_12") (pintype "input"))
    )
    (net (code "134") (name "unconnected-(U4D--IN2-Pad13)") (class "Default")
      (node (ref "U4") (pin "13") (pinfunction "-IN2_13") (pintype "input"))
    )
    (net (code "135") (name "unconnected-(U4D-OUT2-Pad14)") (class "Default")
      (node (ref "U4") (pin "14") (pinfunction "OUT2_14") (pintype "output"))
    )
  )
)
